# Schematics.net
KiCad netlist of a schematic drawn in Altium Designer
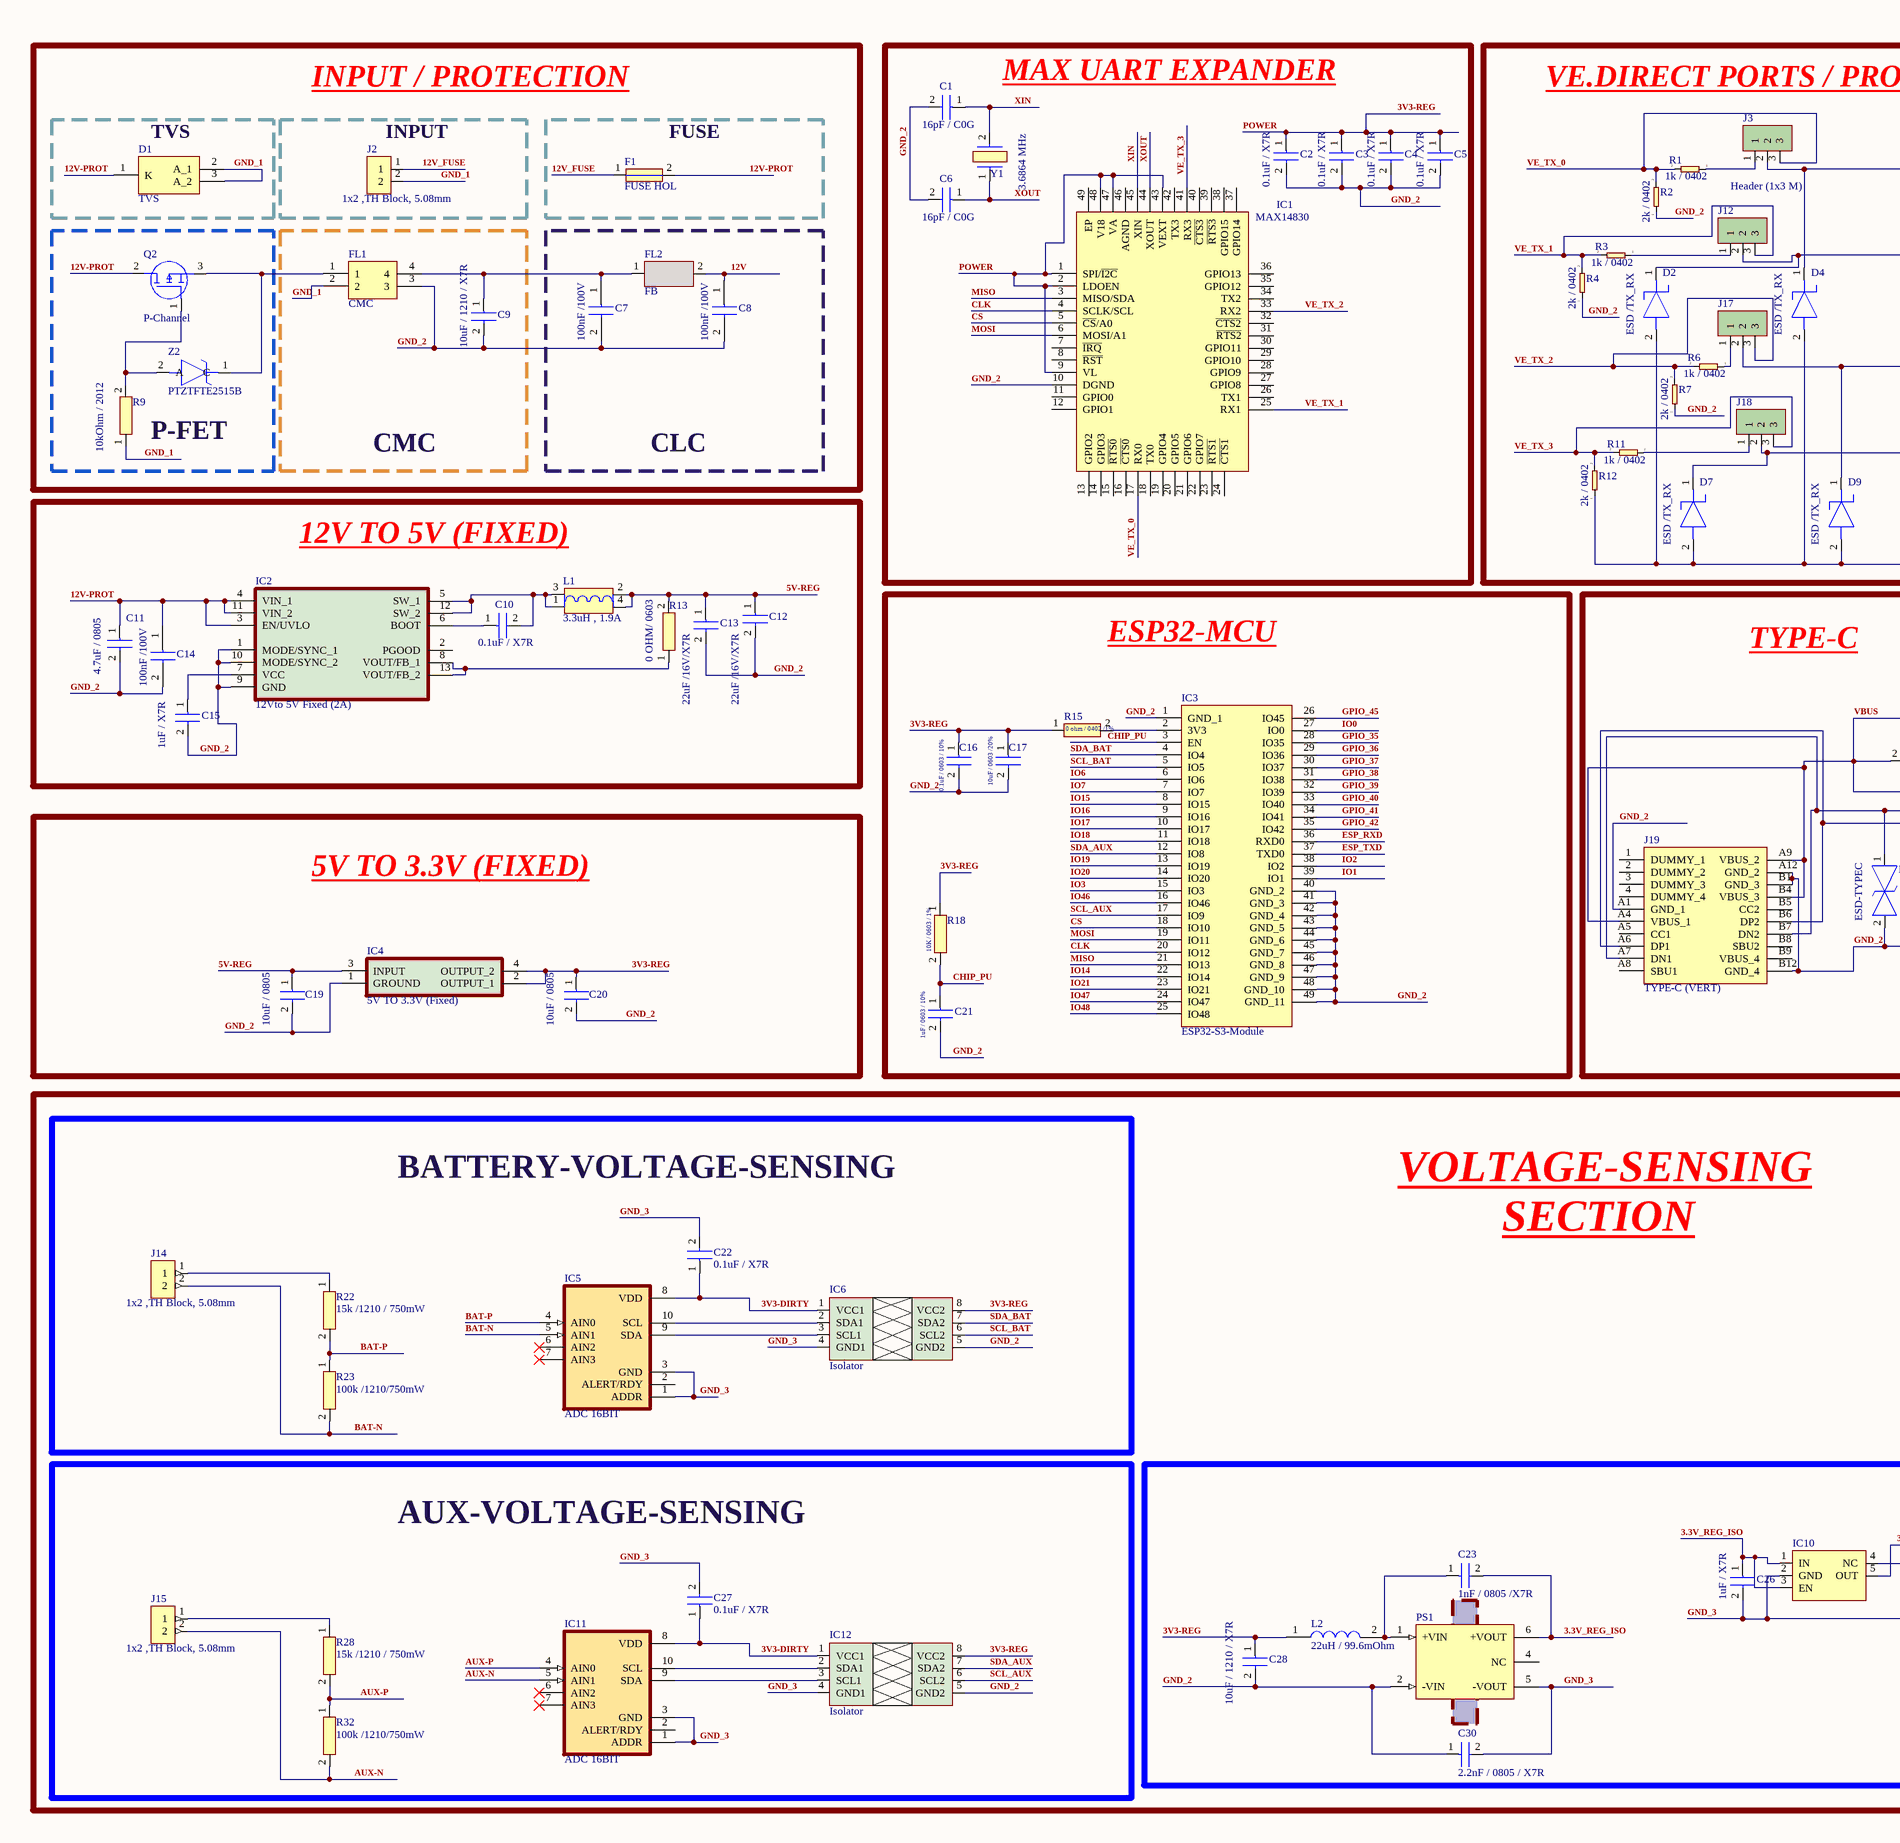
[diagram p0: Schematics.SchDoc, left]
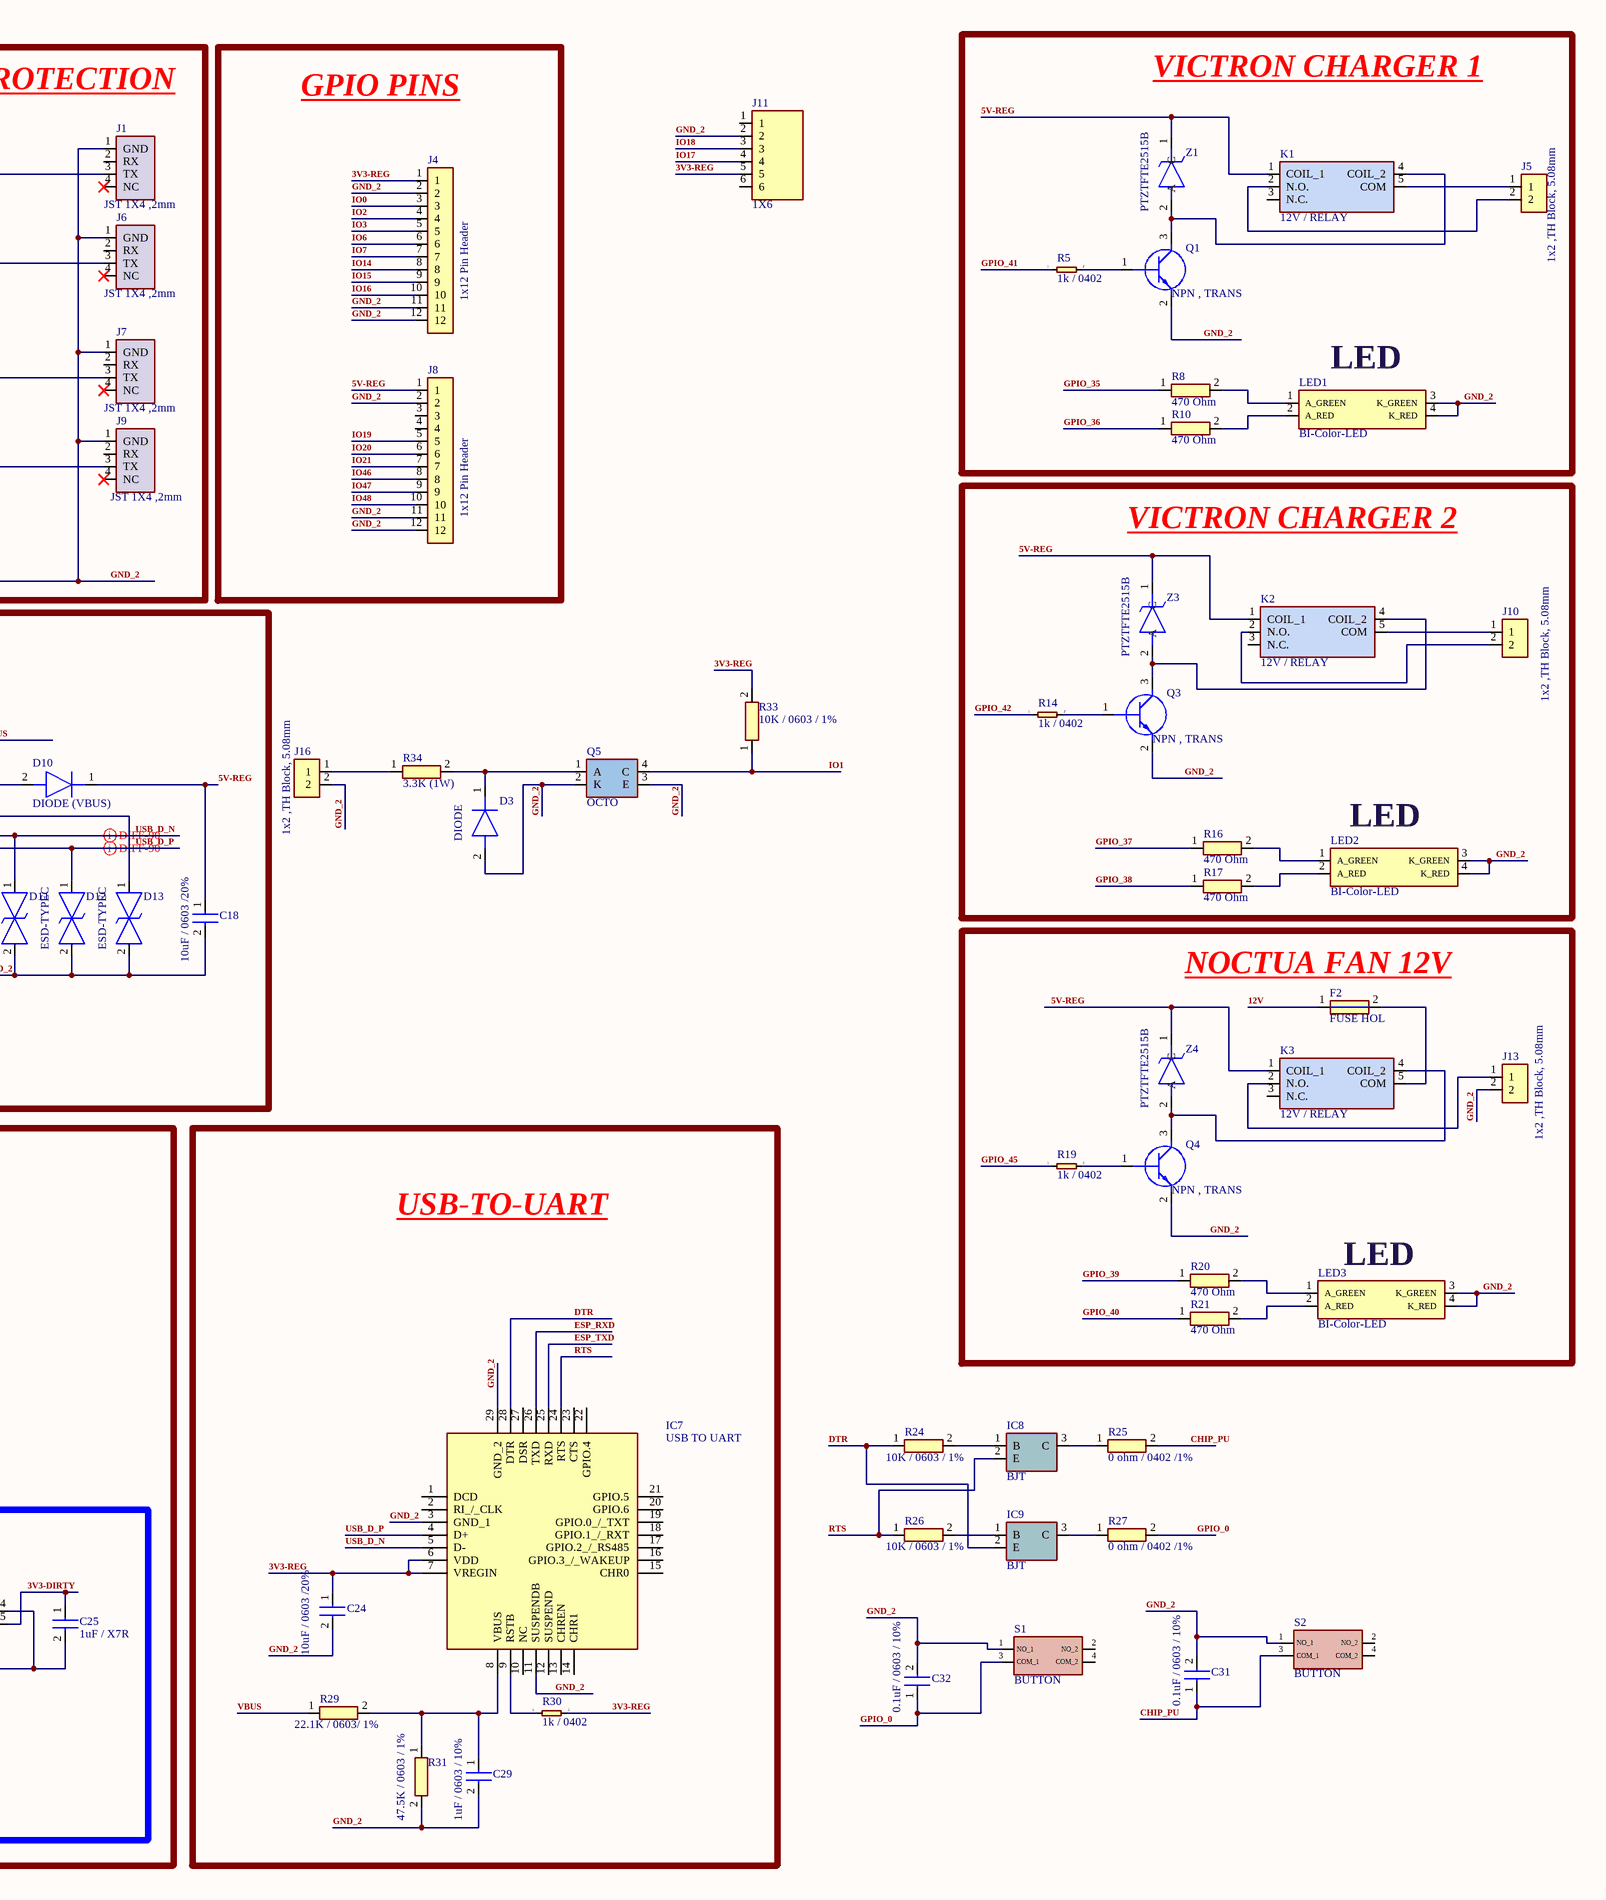
[diagram p1: Schematics.SchDoc, right]

(export (version "E")
  (design (tool "Eeschema 10.0.6"))
  (components
    (comp (ref "C1")
      (value "16pF / C0G")
      (footprint "Project-SCH_Lib:GJM1555C1H170JB01J")
      (description "Capacitor")
      (fields
        (field (name "MANUFACTURER_PART_NUMBER") "GJM1555C1H160FB01J")
        (field (name "MOUSER PART NUMBER") "81-GJM1555C1H160FB1J")
      )
      (libsource (lib "Project-SCH_Lib") (part "GJM1555C1H160FB01J"))
    )
    (comp (ref "C2")
      (value "0.1uF / X7R")
      (footprint "MAJx16")
      (description "Capacitor")
      (fields (field (name "MANUFACTURER_PART_NUMBER") "MAJCU168BB7104KTEA01"))
      (libsource (lib "Project-SCH_Lib") (part "MAJCU168BB7104KTEA01"))
    )
    (comp (ref "C3")
      (value "0.1uF / X7R")
      (footprint "MAJx16")
      (description "Capacitor")
      (fields (field (name "MANUFACTURER_PART_NUMBER") "MAJCU168BB7104KTEA01"))
      (libsource (lib "Project-SCH_Lib") (part "MAJCU168BB7104KTEA01"))
    )
    (comp (ref "C4")
      (value "0.1uF / X7R")
      (footprint "MAJx16")
      (description "Capacitor")
      (fields (field (name "MANUFACTURER_PART_NUMBER") "MAJCU168BB7104KTEA01"))
      (libsource (lib "Project-SCH_Lib") (part "MAJCU168BB7104KTEA01"))
    )
    (comp (ref "C5")
      (value "0.1uF / X7R")
      (footprint "MAJx16")
      (description "Capacitor")
      (fields (field (name "MANUFACTURER_PART_NUMBER") "MAJCU168BB7104KTEA01"))
      (libsource (lib "Project-SCH_Lib") (part "MAJCU168BB7104KTEA01"))
    )
    (comp (ref "C6")
      (value "16pF / C0G")
      (footprint "Project-SCH_Lib:GJM1555C1H170JB01J")
      (description "Capacitor")
      (fields
        (field (name "MANUFACTURER_PART_NUMBER") "GJM1555C1H160FB01J")
        (field (name "MOUSER PART NUMBER") "81-GJM1555C1H160FB1J")
      )
      (libsource (lib "Project-SCH_Lib") (part "GJM1555C1H160FB01J"))
    )
    (comp (ref "C7")
      (value "100nF /100V")
      (footprint "AVCF-PCB_Lib:CAPC1608X87N")
      (description "Multilayer Ceramic Capacitors MLCC - SMD/SMT 100V 100000pF 5% X7R 1608 AEC-Q200")
      (fields
        (field (name "MANUFACTURER_PART_NUMBER") "C0603C104J1RACAUTO7411")
        (field (name "MOUSER PART NUMBER") "80-C0603C104J1RAUTO7")
      )
      (libsource (lib "Project-SCH_Lib") (part "C0603C104J1RACAUTO7411"))
    )
    (comp (ref "C8")
      (value "100nF /100V")
      (footprint "AVCF-PCB_Lib:CAPC1608X87N")
      (description "Multilayer Ceramic Capacitors MLCC - SMD/SMT 100V 100000pF 5% X7R 1608 AEC-Q200")
      (fields
        (field (name "MANUFACTURER_PART_NUMBER") "C0603C104J1RACAUTO7411")
        (field (name "MOUSER PART NUMBER") "80-C0603C104J1RAUTO7")
      )
      (libsource (lib "Project-SCH_Lib") (part "C0603C104J1RACAUTO7411"))
    )
    (comp (ref "C9")
      (value "10uF / 1210 / X7R")
      (footprint "Project-SCH_Lib:CAPC3225X280N")
      (description "Capacitor")
      (fields (field (name "MANUFACTURER_PART_NUMBER") "CGA6P1X7R2A106K250AC"))
      (libsource (lib "Project-SCH_Lib") (part "CGA6P1X7R2A106K250AC"))
    )
    (comp (ref "C10")
      (value "0.1uF / X7R")
      (footprint "MAJx16")
      (description "Capacitor")
      (fields (field (name "MANUFACTURER_PART_NUMBER") "MAJCU168BB7104KTEA01"))
      (libsource (lib "Project-SCH_Lib") (part "MAJCU168BB7104KTEA01"))
    )
    (comp (ref "C11")
      (value "4.7uF / 0805")
      (footprint "AVCF-PCB_Lib:CGA4J2NP01H223J125AA")
      (description "Capacitor")
      (fields
        (field (name "MANUFACTURER_PART_NUMBER") "CGA4J3X7R1C475K125AE")
        (field (name "MOUSER PART NUMBER") "810-CGA4J3X7R1C475KS")
      )
      (libsource (lib "Project-SCH_Lib") (part "CGA4J3X7R1C475K125AE"))
    )
    (comp (ref "C12")
      (value "22uF /16V/X7R")
      (footprint "AVCF-PCB_Lib:CAPC3225X280N")
      (description "Capacitor")
      (fields
        (field (name "MANUFACTURER_PART_NUMBER") "CGA6P1X7R1C226M250AC")
        (field (name "MOUSER PART NUMBER") "810-CGA6P1X7R1C226M")
      )
      (libsource (lib "Project-SCH_Lib") (part "CGA6P1X7R1C226M250AC"))
    )
    (comp (ref "C13")
      (value "22uF /16V/X7R")
      (footprint "AVCF-PCB_Lib:CAPC3225X280N")
      (description "Capacitor")
      (fields
        (field (name "MANUFACTURER_PART_NUMBER") "CGA6P1X7R1C226M250AC")
        (field (name "MOUSER PART NUMBER") "810-CGA6P1X7R1C226M")
      )
      (libsource (lib "Project-SCH_Lib") (part "CGA6P1X7R1C226M250AC"))
    )
    (comp (ref "C14")
      (value "100nF /100V")
      (footprint "AVCF-PCB_Lib:CAPC1608X87N")
      (description "Multilayer Ceramic Capacitors MLCC - SMD/SMT 100V 100000pF 5% X7R 1608 AEC-Q200")
      (fields
        (field (name "MANUFACTURER_PART_NUMBER") "C0603C104J1RACAUTO7411")
        (field (name "MOUSER PART NUMBER") "80-C0603C104J1RAUTO7")
      )
      (libsource (lib "Project-SCH_Lib") (part "C0603C104J1RACAUTO7411"))
    )
    (comp (ref "C15")
      (value "1uF / X7R")
      (footprint "CAPC1608X100N")
      (description "Capacitor")
      (fields
        (field (name "MANUFACTURER_PART_NUMBER") "CL10B105KB9VPNC")
        (field (name "MOUSER PART NUMBER") "187-CL10B105KB9VPNC")
      )
      (libsource (lib "Project-SCH_Lib") (part "CL10B105KB9VPNC"))
    )
    (comp (ref "C16")
      (value "0.1uF / 0603 / 10%")
      (footprint "Project-SCH_Lib:CAPC1608X90N")
      (description "Multilayer Ceramic Capacitors MLCC - SMD/SMT CGA 0603 25V 0.1uF X7R 10% AEC-Q200")
      (fields
        (field (name "MANUFACTURER_PART_NUMBER") "CGA3E2X7R1E104K080AA")
        (field (name "MOUSER PART NUMBER") "810-CGA3E2X7R1E104K")
      )
      (libsource (lib "Project-SCH_Lib") (part "CGA3E2X7R1E104K080AA"))
    )
    (comp (ref "C17")
      (value "10uF / 0603 /20%")
      (footprint "Project-SCH_Lib:CAPC1608X90N")
      (description "Multilayer Ceramic Capacitors MLCC - SMD/SMT 10 uF 25 VDC 20% 0603 X5R AEC-Q200")
      (fields
        (field (name "MANUFACTURER_PART_NUMBER") "GRT188R61E106ME13D")
        (field (name "MOUSER PART NUMBER") "81-GRT188R61E106ME3D")
      )
      (libsource (lib "Project-SCH_Lib") (part "GRT188R61E106ME13D"))
    )
    (comp (ref "C18")
      (value "10uF / 0603 /20%")
      (footprint "Project-SCH_Lib:CAPC1608X90N")
      (description "Multilayer Ceramic Capacitors MLCC - SMD/SMT 10 uF 25 VDC 20% 0603 X5R AEC-Q200")
      (fields
        (field (name "MANUFACTURER_PART_NUMBER") "GRT188R61E106ME13D")
        (field (name "MOUSER PART NUMBER") "81-GRT188R61E106ME3D")
      )
      (libsource (lib "Project-SCH_Lib") (part "GRT188R61E106ME13D"))
    )
    (comp (ref "C19")
      (value "10uF / 0805")
      (footprint "AVCF-PCB_Lib:CGA4J2NP01H223J125AA")
      (description "Capacitor")
      (fields
        (field (name "MANUFACTURER_PART_NUMBER") "CGA4J1X7S1C106M125AE")
        (field (name "MOUSER PART NUMBER") "810-CGA4J1X7S1C106MA")
      )
      (libsource (lib "Project-SCH_Lib") (part "CGA4J1X7S1C106M125AE"))
    )
    (comp (ref "C20")
      (value "10uF / 0805")
      (footprint "AVCF-PCB_Lib:CGA4J2NP01H223J125AA")
      (description "Capacitor")
      (fields
        (field (name "MANUFACTURER_PART_NUMBER") "CGA4J1X7S1C106M125AE")
        (field (name "MOUSER PART NUMBER") "810-CGA4J1X7S1C106MA")
      )
      (libsource (lib "Project-SCH_Lib") (part "CGA4J1X7S1C106M125AE"))
    )
    (comp (ref "C21")
      (value "1uF / 0603 / 10%")
      (footprint "Project-SCH_Lib:CAPC1608X90N")
      (description "Multilayer Ceramic Capacitors MLCC - SMD/SMT SOFT 0603 25V 1uF X7R 10% AEC-Q200")
      (fields
        (field (name "MANUFACTURER_PART_NUMBER") "CGA3E1X7R1E105K080AE")
        (field (name "MOUSER PART NUMBER") "810-CGA3E1X7R1E105KA")
      )
      (libsource (lib "Project-SCH_Lib") (part "CGA3E1X7R1E105K080AE"))
    )
    (comp (ref "C22")
      (value "0.1uF / X7R")
      (footprint "MAJx16")
      (description "Capacitor")
      (fields (field (name "MANUFACTURER_PART_NUMBER") "MAJCU168BB7104KTEA01"))
      (libsource (lib "Project-SCH_Lib") (part "MAJCU168BB7104KTEA01"))
    )
    (comp (ref "C23")
      (value "1nF / 0805 /X7R")
      (footprint "Project-SCH_Lib:C0805")
      (description "Multilayer Ceramic Capacitors MLCC - SMD/SMT 100V 1000pF X7R 0805 20% AEC-Q200")
      (fields
        (field (name "MANUFACTURER_PART_NUMBER") "C0805J222K1RACAUTO")
        (field (name "MOUSER PART NUMBER") "80-C0805J222K1RAUTO")
      )
      (libsource (lib "Project-SCH_Lib") (part "C0805J222K1RACAUTO_1"))
    )
    (comp (ref "C24")
      (value "10uF / 0603 /20%")
      (footprint "Project-SCH_Lib:CAPC1608X90N")
      (description "Multilayer Ceramic Capacitors MLCC - SMD/SMT 10 uF 25 VDC 20% 0603 X5R AEC-Q200")
      (fields
        (field (name "MANUFACTURER_PART_NUMBER") "GRT188R61E106ME13D")
        (field (name "MOUSER PART NUMBER") "81-GRT188R61E106ME3D")
      )
      (libsource (lib "Project-SCH_Lib") (part "GRT188R61E106ME13D"))
    )
    (comp (ref "C25")
      (value "1uF / X7R")
      (footprint "CAPC1608X100N")
      (description "Capacitor")
      (fields
        (field (name "MANUFACTURER_PART_NUMBER") "CL10B105KB9VPNC")
        (field (name "MOUSER PART NUMBER") "187-CL10B105KB9VPNC")
      )
      (libsource (lib "Project-SCH_Lib") (part "CL10B105KB9VPNC"))
    )
    (comp (ref "C26")
      (value "1uF / X7R")
      (footprint "CAPC1608X100N")
      (description "Capacitor")
      (fields
        (field (name "MANUFACTURER_PART_NUMBER") "CL10B105KB9VPNC")
        (field (name "MOUSER PART NUMBER") "187-CL10B105KB9VPNC")
      )
      (libsource (lib "Project-SCH_Lib") (part "CL10B105KB9VPNC"))
    )
    (comp (ref "C27")
      (value "0.1uF / X7R")
      (footprint "MAJx16")
      (description "Capacitor")
      (fields (field (name "MANUFACTURER_PART_NUMBER") "MAJCU168BB7104KTEA01"))
      (libsource (lib "Project-SCH_Lib") (part "MAJCU168BB7104KTEA01"))
    )
    (comp (ref "C28")
      (value "10uF / 1210 / X7R")
      (footprint "Project-SCH_Lib:CAPC3225X280N")
      (description "Capacitor")
      (fields (field (name "MANUFACTURER_PART_NUMBER") "CGA6P1X7R2A106K250AC"))
      (libsource (lib "Project-SCH_Lib") (part "CGA6P1X7R2A106K250AC"))
    )
    (comp (ref "C29")
      (value "1uF / 0603 / 10%")
      (footprint "Project-SCH_Lib:CAPC1608X90N")
      (description "Multilayer Ceramic Capacitors MLCC - SMD/SMT SOFT 0603 25V 1uF X7R 10% AEC-Q200")
      (fields
        (field (name "MANUFACTURER_PART_NUMBER") "CGA3E1X7R1E105K080AE")
        (field (name "MOUSER PART NUMBER") "810-CGA3E1X7R1E105KA")
      )
      (libsource (lib "Project-SCH_Lib") (part "CGA3E1X7R1E105K080AE"))
    )
    (comp (ref "C30")
      (value "2.2nF / 0805 / X7R")
      (footprint "Project-SCH_Lib:C0805")
      (description "Multilayer Ceramic Capacitors MLCC - SMD/SMT 100V 2200pF X7R 0805 10% AEC-Q200")
      (fields
        (field (name "MANUFACTURER_PART_NUMBER") "C0805J222K1RACAUTO")
        (field (name "MOUSER PART NUMBER") "80-C0805J222K1RAUTO")
      )
      (libsource (lib "Project-SCH_Lib") (part "C0805J222K1RACAUTO"))
    )
    (comp (ref "C31")
      (value "0.1uF / 0603 / 10%")
      (footprint "Project-SCH_Lib:CAPC1608X90N")
      (description "Multilayer Ceramic Capacitors MLCC - SMD/SMT CGA 0603 25V 0.1uF X7R 10% AEC-Q200")
      (fields
        (field (name "MANUFACTURER_PART_NUMBER") "CGA3E2X7R1E104K080AA")
        (field (name "MOUSER PART NUMBER") "810-CGA3E2X7R1E104K")
      )
      (libsource (lib "Project-SCH_Lib") (part "CGA3E2X7R1E104K080AA"))
    )
    (comp (ref "C32")
      (value "0.1uF / 0603 / 10%")
      (footprint "Project-SCH_Lib:CAPC1608X90N")
      (description "Multilayer Ceramic Capacitors MLCC - SMD/SMT CGA 0603 25V 0.1uF X7R 10% AEC-Q200")
      (fields
        (field (name "MANUFACTURER_PART_NUMBER") "CGA3E2X7R1E104K080AA")
        (field (name "MOUSER PART NUMBER") "810-CGA3E2X7R1E104K")
      )
      (libsource (lib "Project-SCH_Lib") (part "CGA3E2X7R1E104K080AA"))
    )
    (comp (ref "D1")
      (value "TVS")
      (footprint "AVCF-PCB_Lib:SLD8S36A")
      (description "TVS Diode (Uni-directional)")
      (fields
        (field (name "MANUFACTURER_PART_NUMBER") "SLD8S36A")
        (field (name "MOUSER PART NUMBER") "576-SLD8S36A")
      )
      (libsource (lib "Project-SCH_Lib") (part "SLD8S36A"))
    )
    (comp (ref "D2")
      (value "ESD /TX_RX")
      (footprint "Project-SCH_Lib:PESD5V0S1ULQYL")
      (description "Diode ESD (Uni-directional)")
      (fields
        (field (name "MANUFACTURER_PART_NUMBER") "PESD5V0S1UL-QYL")
        (field (name "MOUSER PART NUMBER") "771-PESD5V0S1UL-QYL")
      )
      (libsource (lib "Project-SCH_Lib") (part "PESD5V0S1UL-QYL"))
    )
    (comp (ref "D3")
      (value "DIODE")
      (footprint "Project-SCH_Lib:SOD3716X125N")
      (description "Diode")
      (fields (field (name "MANUFACTURER_PART_NUMBER") "1N5819HW-7-F"))
      (libsource (lib "Project-SCH_Lib") (part "1N5819HW-7-F"))
    )
    (comp (ref "D4")
      (value "ESD /TX_RX")
      (footprint "Project-SCH_Lib:PESD5V0S1ULQYL")
      (description "Diode ESD (Uni-directional)")
      (fields
        (field (name "MANUFACTURER_PART_NUMBER") "PESD5V0S1UL-QYL")
        (field (name "MOUSER PART NUMBER") "771-PESD5V0S1UL-QYL")
      )
      (libsource (lib "Project-SCH_Lib") (part "PESD5V0S1UL-QYL"))
    )
    (comp (ref "D7")
      (value "ESD /TX_RX")
      (footprint "Project-SCH_Lib:PESD5V0S1ULQYL")
      (description "Diode ESD (Uni-directional)")
      (fields
        (field (name "MANUFACTURER_PART_NUMBER") "PESD5V0S1UL-QYL")
        (field (name "MOUSER PART NUMBER") "771-PESD5V0S1UL-QYL")
      )
      (libsource (lib "Project-SCH_Lib") (part "PESD5V0S1UL-QYL"))
    )
    (comp (ref "D9")
      (value "ESD /TX_RX")
      (footprint "Project-SCH_Lib:PESD5V0S1ULQYL")
      (description "Diode ESD (Uni-directional)")
      (fields
        (field (name "MANUFACTURER_PART_NUMBER") "PESD5V0S1UL-QYL")
        (field (name "MOUSER PART NUMBER") "771-PESD5V0S1UL-QYL")
      )
      (libsource (lib "Project-SCH_Lib") (part "PESD5V0S1UL-QYL"))
    )
    (comp (ref "D10")
      (value "DIODE (VBUS)")
      (footprint "Project-SCH_Lib:SOD3716X125N")
      (description "Diode")
      (fields (field (name "MANUFACTURER_PART_NUMBER") "1N5819HW-7-F"))
      (libsource (lib "Project-SCH_Lib") (part "1N5819HW-7-F"))
    )
    (comp (ref "D11")
      (value "ESD-TYPEC")
      (footprint "Project-SCH_Lib:LESD5D50CT1G")
      (description "TVS Diode (Bi-directional)")
      (fields (field (name "MANUFACTURER_PART_NUMBER") "LESD5D5.0CT1G"))
      (libsource (lib "Project-SCH_Lib") (part "LESD5D5.0CT1G"))
    )
    (comp (ref "D12")
      (value "ESD-TYPEC")
      (footprint "Project-SCH_Lib:LESD5D50CT1G")
      (description "TVS Diode (Bi-directional)")
      (fields (field (name "MANUFACTURER_PART_NUMBER") "LESD5D5.0CT1G"))
      (libsource (lib "Project-SCH_Lib") (part "LESD5D5.0CT1G"))
    )
    (comp (ref "D13")
      (value "ESD-TYPEC")
      (footprint "Project-SCH_Lib:LESD5D50CT1G")
      (description "TVS Diode (Bi-directional)")
      (fields (field (name "MANUFACTURER_PART_NUMBER") "LESD5D5.0CT1G"))
      (libsource (lib "Project-SCH_Lib") (part "LESD5D5.0CT1G"))
    )
    (comp (ref "F1")
      (value "FUSE HOL")
      (footprint "ESP-P4-PCB_LIB:01530008")
      (description "Fuse Holder 15 A 32V 1 Circuit Blade Through Hole")
      (fields
        (field (name "MANUFACTURER_PART_NUMBER") "01530008Z")
        (field (name "MOUSER PART NUMBER") "576-01530008Z")
      )
      (libsource (lib "Project-SCH_Lib") (part "01530008Z"))
    )
    (comp (ref "F2")
      (value "FUSE HOL")
      (footprint "ESP-P4-PCB_LIB:01530008")
      (description "Fuse Holder 15 A 32V 1 Circuit Blade Through Hole")
      (fields
        (field (name "MANUFACTURER_PART_NUMBER") "01530008Z")
        (field (name "MOUSER PART NUMBER") "576-01530008Z")
      )
      (libsource (lib "Project-SCH_Lib") (part "01530008Z"))
    )
    (comp (ref "FL1")
      (value "CMC")
      (footprint "ACT45B1012PTL003")
      (description "Filter")
      (fields
        (field (name "MANUFACTURER_PART_NUMBER") "ACT45B-510-2P-TL003")
        (field (name "MOUSER PART NUMBER") "810-ACT45B5102PTL003")
      )
      (libsource (lib "Project-SCH_Lib") (part "ACT45B-510-2P-TL003"))
    )
    (comp (ref "FL2")
      (value "FB")
      (footprint "BLM31KN102BH1L")
      (description "Filter")
      (fields
        (field (name "MANUFACTURER_PART_NUMBER") "BLM31KN601SZ1L")
        (field (name "MOUSER PART NUMBER") "81-BLM31KN601SZ1L")
      )
      (libsource (lib "Project-SCH_Lib") (part "BLM31KN601SZ1L"))
    )
    (comp (ref "IC1")
      (value "MAX14830")
      (footprint "Project-SCH_Lib:QFN50P700X700X80-49N")
      (description "UART Interface IC Quad Serial UART")
      (fields
        (field (name "MANUFACTURER_PART_NUMBER") "MAX14830ETM+")
        (field (name "MOUSER PART NUMBER") "700-MAX14830ETM+")
      )
      (libsource (lib "Project-SCH_Lib") (part "MAX14830ETM+"))
    )
    (comp (ref "IC2")
      (value "12Vto 5V Fixed (2A)")
      (footprint "Project-SCH_Lib:LMR43620MC5RPERQ1")
      (description "Integrated Circuit")
      (fields (field (name "MANUFACTURER_PART_NUMBER") "LMR43620MSC5RPERQ1"))
      (libsource (lib "Project-SCH_Lib") (part "LMR43620MSC5RPERQ1"))
    )
    (comp (ref "IC3")
      (value "ESP32-S3-Module")
      (footprint "Project-SCH_Lib:ESP32S3WROOM1N8R2")
      (description "WiFi 802.11a/b/g/n, Bluetooth v5.0 Transceiver Module 2.4GHz PCB Trace")
      (fields
        (field (name "MANUFACTURER_PART_NUMBER") "ESP32-S3-WROOM-1-N8")
        (field (name "MOUSER PART NUMBER") "356-ESP32-S3WROOM1N8")
      )
      (libsource (lib "Project-SCH_Lib") (part "ESP32-S3-WROOM-1-N8"))
    )
    (comp (ref "IC4")
      (value "5V TO 3.3V (Fixed)")
      (footprint "Project-SCH_Lib:SOT230P700X180-4N")
      (description "Integrated Circuit")
      (fields
        (field (name "MANUFACTURER_PART_NUMBER") "NCV1117ST33T3G")
        (field (name "MOUSER PART NUMBER") "863-NCV1117ST33T3G")
      )
      (libsource (lib "Project-SCH_Lib") (part "NCV1117ST33T3G"))
    )
    (comp (ref "IC5")
      (value "ADC 16BIT")
      (footprint "Project-SCH_Lib:RUG-(R-PQFP-N10)")
      (description "16 Bit Analog to Digital Converter 2, 4 Input 1 Sigma-Delta 10-X2QFN (2x1.5)")
      (fields
        (field (name "MANUFACTURER_PART_NUMBER") "ADS1115IRUGT")
        (field (name "MOUSER PART NUMBER") "595-ADS1115IRUGT")
      )
      (libsource (lib "Project-SCH_Lib") (part "ADS1115IRUGT"))
    )
    (comp (ref "IC6")
      (value "Isolator")
      (footprint "Project-SCH_Lib:SOIC127P600X175-8N")
      (description "Integrated Circuit")
      (fields
        (field (name "MANUFACTURER_PART_NUMBER") "ISO1540DR")
        (field (name "MOUSER PART NUMBER") "595-ISO1540DR")
      )
      (libsource (lib "Project-SCH_Lib") (part "ISO1540DR"))
    )
    (comp (ref "IC7")
      (value "USB TO UART")
      (footprint "Project-SCH_Lib:QFN50P500X500X80-29N-D")
      (description "USB Bridge, USB to UART USB 2.0 UART Interface 28-QFN (5x5)")
      (fields
        (field (name "MANUFACTURER_PART_NUMBER") "CP2102N-A02-GQFN28R")
        (field (name "MOUSER PART NUMBER") "634-CP2102NA02QFN28R")
      )
      (libsource (lib "Project-SCH_Lib") (part "CP2102N-A02-GQFN28R"))
    )
    (comp (ref "IC8")
      (value "BJT")
      (footprint "SamacSys:L8050QLT1G")
      (description "Integrated Circuit")
      (fields (field (name "MANUFACTURER_PART_NUMBER") "L8050QLT1G"))
      (libsource (lib "Project-SCH_Lib") (part "L8050QLT1G"))
    )
    (comp (ref "IC9")
      (value "BJT")
      (footprint "SamacSys:L8050QLT1G")
      (description "Integrated Circuit")
      (fields (field (name "MANUFACTURER_PART_NUMBER") "L8050QLT1G"))
      (libsource (lib "Project-SCH_Lib") (part "L8050QLT1G"))
    )
    (comp (ref "IC10")
      (value "~")
      (footprint "SOT95P280X145-5N")
      (description "Linear Voltage Regulator IC Positive Fixed 1 Output 300mA SOT-23-5")
      (fields
        (field (name "MANUFACTURER_PART_NUMBER") "TLV70233PDBVT")
        (field (name "MOUSER PART NUMBER") "595-TLV70233PDBVT")
      )
      (libsource (lib "Project-SCH_Lib") (part "TLV70233PDBVT"))
    )
    (comp (ref "IC11")
      (value "ADC 16BIT")
      (footprint "Project-SCH_Lib:RUG-(R-PQFP-N10)")
      (description "16 Bit Analog to Digital Converter 2, 4 Input 1 Sigma-Delta 10-X2QFN (2x1.5)")
      (fields
        (field (name "MANUFACTURER_PART_NUMBER") "ADS1115IRUGT")
        (field (name "MOUSER PART NUMBER") "595-ADS1115IRUGT")
      )
      (libsource (lib "Project-SCH_Lib") (part "ADS1115IRUGT"))
    )
    (comp (ref "IC12")
      (value "Isolator")
      (footprint "Project-SCH_Lib:SOIC127P600X175-8N")
      (description "Integrated Circuit")
      (fields
        (field (name "MANUFACTURER_PART_NUMBER") "ISO1540DR")
        (field (name "MOUSER PART NUMBER") "595-ISO1540DR")
      )
      (libsource (lib "Project-SCH_Lib") (part "ISO1540DR"))
    )
    (comp (ref "J1")
      (value "JST 1X4 ,2mm")
      (footprint "Project-SCH_Lib:SHDR4W50P0X200_1X4_990X600X450P")
      (description "Connector")
      (fields (field (name "MANUFACTURER_PART_NUMBER") "455-1706-ND"))
      (libsource (lib "Project-SCH_Lib") (part "455-1706-ND"))
    )
    (comp (ref "J2")
      (value "1x2 ,TH Block, 5.08mm")
      (footprint "Project-SCH_Lib:1760510000")
      (description "2 Position Wire to Board Terminal Block Horizontal with Board 0.200\" (5.08mm) Through Hole")
      (fields
        (field (name "MANUFACTURER_PART_NUMBER") "1760510000")
        (field (name "MOUSER PART NUMBER") "470-1760510000")
      )
      (libsource (lib "") (part "1760510000_1"))
    )
    (comp (ref "J3")
      (value "Header (1x3 M)")
      (footprint "Project-SCH_Lib:HDRV3W63P0X254_1X3_762X250X950P")
      (description "Connector")
      (fields
        (field (name "MANUFACTURER_PART_NUMBER") "826926-3")
        (field (name "MOUSER PART NUMBER") "571-826926-3")
      )
      (libsource (lib "Project-SCH_Lib") (part "826926-3"))
    )
    (comp (ref "J4")
      (value "1x12 Pin Header")
      (footprint "Project-SCH_Lib:HDRV12W68P0X254_1X12_3048X250X970P")
      (description "Connector")
      (fields
        (field (name "MANUFACTURER_PART_NUMBER") "1-826629-2")
        (field (name "MOUSER PART NUMBER") "571-1-826629-2")
      )
      (libsource (lib "Project-SCH_Lib") (part "1-826629-2"))
    )
    (comp (ref "J5")
      (value "1x2 ,TH Block, 5.08mm")
      (footprint "Project-SCH_Lib:1760510000")
      (description "2 Position Wire to Board Terminal Block Horizontal with Board 0.200\" (5.08mm) Through Hole")
      (fields
        (field (name "MANUFACTURER_PART_NUMBER") "1760510000")
        (field (name "MOUSER PART NUMBER") "470-1760510000")
      )
      (libsource (lib "Project-SCH_Lib") (part "1760510000"))
    )
    (comp (ref "J6")
      (value "JST 1X4 ,2mm")
      (footprint "Project-SCH_Lib:SHDR4W50P0X200_1X4_990X600X450P")
      (description "Connector")
      (fields (field (name "MANUFACTURER_PART_NUMBER") "455-1706-ND"))
      (libsource (lib "Project-SCH_Lib") (part "455-1706-ND"))
    )
    (comp (ref "J7")
      (value "JST 1X4 ,2mm")
      (footprint "Project-SCH_Lib:SHDR4W50P0X200_1X4_990X600X450P")
      (description "Connector")
      (fields (field (name "MANUFACTURER_PART_NUMBER") "455-1706-ND"))
      (libsource (lib "Project-SCH_Lib") (part "455-1706-ND"))
    )
    (comp (ref "J8")
      (value "1x12 Pin Header")
      (footprint "Project-SCH_Lib:HDRV12W68P0X254_1X12_3048X250X970P")
      (description "Connector")
      (fields
        (field (name "MANUFACTURER_PART_NUMBER") "1-826629-2")
        (field (name "MOUSER PART NUMBER") "571-1-826629-2")
      )
      (libsource (lib "Project-SCH_Lib") (part "1-826629-2"))
    )
    (comp (ref "J9")
      (value "JST 1X4 ,2mm")
      (footprint "Project-SCH_Lib:SHDR4W50P0X200_1X4_990X600X450P")
      (description "Connector")
      (fields (field (name "MANUFACTURER_PART_NUMBER") "455-1706-ND"))
      (libsource (lib "Project-SCH_Lib") (part "455-1706-ND"))
    )
    (comp (ref "J10")
      (value "1x2 ,TH Block, 5.08mm")
      (footprint "Project-SCH_Lib:1760510000")
      (description "2 Position Wire to Board Terminal Block Horizontal with Board 0.200\" (5.08mm) Through Hole")
      (fields
        (field (name "MANUFACTURER_PART_NUMBER") "1760510000")
        (field (name "MOUSER PART NUMBER") "470-1760510000")
      )
      (libsource (lib "Project-SCH_Lib") (part "1760510000"))
    )
    (comp (ref "J11")
      (value "1X6")
      (footprint "Project-SCH_Lib:68001206HLF")
      (description "Connector")
      (fields
        (field (name "MANUFACTURER_PART_NUMBER") "68001-206HLF")
        (field (name "MOUSER PART NUMBER") "649-68001-206HLF")
      )
      (libsource (lib "Project-SCH_Lib") (part "68001-206HLF"))
    )
    (comp (ref "J12")
      (value "Header (1x3 M)")
      (footprint "Project-SCH_Lib:HDRV3W63P0X254_1X3_762X250X950P")
      (description "Connector")
      (fields
        (field (name "MANUFACTURER_PART_NUMBER") "826926-3")
        (field (name "MOUSER PART NUMBER") "571-826926-3")
      )
      (libsource (lib "Project-SCH_Lib") (part "826926-3"))
    )
    (comp (ref "J13")
      (value "1x2 ,TH Block, 5.08mm")
      (footprint "Project-SCH_Lib:1760510000")
      (description "2 Position Wire to Board Terminal Block Horizontal with Board 0.200\" (5.08mm) Through Hole")
      (fields
        (field (name "MANUFACTURER_PART_NUMBER") "1760510000")
        (field (name "MOUSER PART NUMBER") "470-1760510000")
      )
      (libsource (lib "Project-SCH_Lib") (part "1760510000"))
    )
    (comp (ref "J14")
      (value "1x2 ,TH Block, 5.08mm")
      (footprint "Project-SCH_Lib:1760510000")
      (description "2 Position Wire to Board Terminal Block Horizontal with Board 0.200\" (5.08mm) Through Hole")
      (fields
        (field (name "MANUFACTURER_PART_NUMBER") "1760510000")
        (field (name "MOUSER PART NUMBER") "470-1760510000")
      )
      (libsource (lib "") (part "1760510000_1"))
    )
    (comp (ref "J15")
      (value "1x2 ,TH Block, 5.08mm")
      (footprint "Project-SCH_Lib:1760510000")
      (description "2 Position Wire to Board Terminal Block Horizontal with Board 0.200\" (5.08mm) Through Hole")
      (fields
        (field (name "MANUFACTURER_PART_NUMBER") "1760510000")
        (field (name "MOUSER PART NUMBER") "470-1760510000")
      )
      (libsource (lib "") (part "1760510000_1"))
    )
    (comp (ref "J16")
      (value "1x2 ,TH Block, 5.08mm")
      (footprint "Project-SCH_Lib:1760510000")
      (description "2 Position Wire to Board Terminal Block Horizontal with Board 0.200\" (5.08mm) Through Hole")
      (fields
        (field (name "MANUFACTURER_PART_NUMBER") "1760510000")
        (field (name "MOUSER PART NUMBER") "470-1760510000")
      )
      (libsource (lib "") (part "1760510000_1"))
    )
    (comp (ref "J17")
      (value "Header (1x3 M)")
      (footprint "Project-SCH_Lib:HDRV3W63P0X254_1X3_762X250X950P")
      (description "Connector")
      (fields
        (field (name "MANUFACTURER_PART_NUMBER") "826926-3")
        (field (name "MOUSER PART NUMBER") "571-826926-3")
      )
      (libsource (lib "Project-SCH_Lib") (part "826926-3"))
    )
    (comp (ref "J18")
      (value "Header (1x3 M)")
      (footprint "Project-SCH_Lib:HDRV3W63P0X254_1X3_762X250X950P")
      (description "Connector")
      (fields
        (field (name "MANUFACTURER_PART_NUMBER") "826926-3")
        (field (name "MOUSER PART NUMBER") "571-826926-3")
      )
      (libsource (lib "Project-SCH_Lib") (part "826926-3"))
    )
    (comp (ref "J19")
      (value "TYPE-C (VERT)")
      (footprint "Project-SCH_Lib:UJ20CVGSMTP16TR65")
      (description "USB Connectors Type C, 2.0, Vertical, Gold Plated 3u, Surface Mount, 16 pin, IP65")
      (fields
        (field (name "MANUFACTURER_PART_NUMBER") "UJ20-C-V-G-SMT-P16-TR-65")
        (field (name "MOUSER PART NUMBER") "179-UJ20CVGSMTP16TR6")
      )
      (libsource (lib "Project-SCH_Lib") (part "UJ20-C-V-G-SMT-P16-TR-65"))
    )
    (comp (ref "K1")
      (value "12V / RELAY")
      (footprint "Project-SCH_Lib:ACQ131")
      (description "Relay or Contactor")
      (fields
        (field (name "MANUFACTURER_PART_NUMBER") "ACQ131")
        (field (name "MOUSER PART NUMBER") "769-ACQ131")
      )
      (libsource (lib "Project-SCH_Lib") (part "ACQ131"))
    )
    (comp (ref "K2")
      (value "12V / RELAY")
      (footprint "Project-SCH_Lib:ACQ131")
      (description "Relay or Contactor")
      (fields
        (field (name "MANUFACTURER_PART_NUMBER") "ACQ131")
        (field (name "MOUSER PART NUMBER") "769-ACQ131")
      )
      (libsource (lib "Project-SCH_Lib") (part "ACQ131"))
    )
    (comp (ref "K3")
      (value "12V / RELAY")
      (footprint "Project-SCH_Lib:ACQ131")
      (description "Relay or Contactor")
      (fields
        (field (name "MANUFACTURER_PART_NUMBER") "ACQ131")
        (field (name "MOUSER PART NUMBER") "769-ACQ131")
      )
      (libsource (lib "Project-SCH_Lib") (part "ACQ131"))
    )
    (comp (ref "L1")
      (value "3.3uH , 1.9A")
      (footprint "Project-SCH_Lib:LQH43MN470K03L")
      (description "Inductor")
      (fields
        (field (name "MANUFACTURER_PART_NUMBER") "LQH43PH3R3M26L")
        (field (name "MOUSER PART NUMBER") "81-LQH43PH3R3M26L")
      )
      (libsource (lib "Project-SCH_Lib") (part "LQH43PH3R3M26L"))
    )
    (comp (ref "L2")
      (value "22uH / 99.6mOhm")
      (footprint "XAL5030")
      (description "Inductor")
      (fields
        (field (name "MANUFACTURER_PART_NUMBER") "XAL5050-223MEC")
        (field (name "MOUSER PART NUMBER") "994-XAL5050-223MEC")
      )
      (libsource (lib "Project-SCH_Lib") (part "XAL5050-223MEC"))
    )
    (comp (ref "LED1")
      (value "BI-Color-LED")
      (footprint "Project-SCH_Lib:HSMFC163")
      (description "LED")
      (fields
        (field (name "MANUFACTURER_PART_NUMBER") "HSMF-C163")
        (field (name "MOUSER PART NUMBER") "630-HSMF-C163")
      )
      (libsource (lib "Project-SCH_Lib") (part "HSMF-C163"))
    )
    (comp (ref "LED2")
      (value "BI-Color-LED")
      (footprint "Project-SCH_Lib:HSMFC163")
      (description "LED")
      (fields
        (field (name "MANUFACTURER_PART_NUMBER") "HSMF-C163")
        (field (name "MOUSER PART NUMBER") "630-HSMF-C163")
      )
      (libsource (lib "Project-SCH_Lib") (part "HSMF-C163"))
    )
    (comp (ref "LED3")
      (value "BI-Color-LED")
      (footprint "Project-SCH_Lib:HSMFC163")
      (description "LED")
      (fields
        (field (name "MANUFACTURER_PART_NUMBER") "HSMF-C163")
        (field (name "MOUSER PART NUMBER") "630-HSMF-C163")
      )
      (libsource (lib "Project-SCH_Lib") (part "HSMF-C163"))
    )
    (comp (ref "PS1")
      (value "~")
      (footprint "CONV_RB-3.33.3S")
      (description "1W DC/DC-Converter 'ECONOLINE' SIP7 1kV unreg")
      (fields (field (name "MF") "Recom Power") (field (name "MP") "RB-3.33.3S"))
      (libsource (lib "Project-SCH_Lib") (part "RB-3.33.3S"))
    )
    (comp (ref "Q1")
      (value "NPN , TRANS")
      (footprint "Project-SCH_Lib:SOT95P230X110-3N")
      (description "Transistor BJT NPN")
      (fields
        (field (name "MANUFACTURER_PART_NUMBER") "DI13001")
        (field (name "MOUSER PART NUMBER") "637-DI13001")
      )
      (libsource (lib "Project-SCH_Lib") (part "DI13001"))
    )
    (comp (ref "Q2")
      (value "P-Channel")
      (footprint "FQD20N06TM")
      (description "MOSFET (P-Channel)")
      (fields
        (field (name "MANUFACTURER_PART_NUMBER") "FQD8P10TM-F085")
        (field (name "MOUSER PART NUMBER") "512-FQD8P10TM_F085")
      )
      (libsource (lib "Project-SCH_Lib") (part "FQD8P10TM-F085"))
    )
    (comp (ref "Q3")
      (value "NPN , TRANS")
      (footprint "Project-SCH_Lib:SOT95P230X110-3N")
      (description "Transistor BJT NPN")
      (fields
        (field (name "MANUFACTURER_PART_NUMBER") "DI13001")
        (field (name "MOUSER PART NUMBER") "637-DI13001")
      )
      (libsource (lib "Project-SCH_Lib") (part "DI13001"))
    )
    (comp (ref "Q4")
      (value "NPN , TRANS")
      (footprint "Project-SCH_Lib:SOT95P230X110-3N")
      (description "Transistor BJT NPN")
      (fields
        (field (name "MANUFACTURER_PART_NUMBER") "DI13001")
        (field (name "MOUSER PART NUMBER") "637-DI13001")
      )
      (libsource (lib "Project-SCH_Lib") (part "DI13001"))
    )
    (comp (ref "Q5")
      (value "OCTO")
      (footprint "Project-SCH_Lib:SOP254P1016X436-4N")
      (description "Phototransistor")
      (fields
        (field (name "MANUFACTURER_PART_NUMBER") "PC817X1CSP9F")
        (field (name "MOUSER PART NUMBER") "852-PC817X1CSP9F")
      )
      (libsource (lib "Project-SCH_Lib") (part "PC817X1CSP9F"))
    )
    (comp (ref "R1")
      (value "1k / 0402")
      (footprint "Project-SCH_Lib:ERJ2RKD1004X")
      (description "Thick Film Resistors - SMD 0402 1Kohms 1% AEC-Q200")
      (fields
        (field (name "MANUFACTURER_PART_NUMBER") "ERJ-2RKF1001X")
        (field (name "MOUSER PART NUMBER") "667-ERJ-2RKF1001X")
      )
      (libsource (lib "") (part "ERJ-2RKF1001X_1"))
    )
    (comp (ref "R2")
      (value "2k / 0402")
      (footprint "Project-SCH_Lib:ERJPA2_(0402)")
      (description "Thick Film Resistors - SMD 0402 1%2Kohm")
      (fields
        (field (name "MANUFACTURER_PART_NUMBER") "ERJ-PA2F2001X")
        (field (name "MOUSER PART NUMBER") "667-ERJ-PA2F2001X")
      )
      (libsource (lib "Project-SCH_Lib") (part "ERJ-PA2F2001X"))
    )
    (comp (ref "R3")
      (value "1k / 0402")
      (footprint "Project-SCH_Lib:ERJ2RKD1004X")
      (description "Thick Film Resistors - SMD 0402 1Kohms 1% AEC-Q200")
      (fields
        (field (name "MANUFACTURER_PART_NUMBER") "ERJ-2RKF1001X")
        (field (name "MOUSER PART NUMBER") "667-ERJ-2RKF1001X")
      )
      (libsource (lib "") (part "ERJ-2RKF1001X_1"))
    )
    (comp (ref "R4")
      (value "2k / 0402")
      (footprint "Project-SCH_Lib:ERJPA2_(0402)")
      (description "Thick Film Resistors - SMD 0402 1%2Kohm")
      (fields
        (field (name "MANUFACTURER_PART_NUMBER") "ERJ-PA2F2001X")
        (field (name "MOUSER PART NUMBER") "667-ERJ-PA2F2001X")
      )
      (libsource (lib "Project-SCH_Lib") (part "ERJ-PA2F2001X"))
    )
    (comp (ref "R5")
      (value "1k / 0402")
      (footprint "Project-SCH_Lib:ERJ2RKD1004X")
      (description "Thick Film Resistors - SMD 0402 1Kohms 1% AEC-Q200")
      (fields
        (field (name "MANUFACTURER_PART_NUMBER") "ERJ-2RKF1001X")
        (field (name "MOUSER PART NUMBER") "667-ERJ-2RKF1001X")
      )
      (libsource (lib "Project-SCH_Lib") (part "ERJ-2RKF1001X"))
    )
    (comp (ref "R6")
      (value "1k / 0402")
      (footprint "Project-SCH_Lib:ERJ2RKD1004X")
      (description "Thick Film Resistors - SMD 0402 1Kohms 1% AEC-Q200")
      (fields
        (field (name "MANUFACTURER_PART_NUMBER") "ERJ-2RKF1001X")
        (field (name "MOUSER PART NUMBER") "667-ERJ-2RKF1001X")
      )
      (libsource (lib "") (part "ERJ-2RKF1001X_1"))
    )
    (comp (ref "R7")
      (value "2k / 0402")
      (footprint "Project-SCH_Lib:ERJPA2_(0402)")
      (description "Thick Film Resistors - SMD 0402 1%2Kohm")
      (fields
        (field (name "MANUFACTURER_PART_NUMBER") "ERJ-PA2F2001X")
        (field (name "MOUSER PART NUMBER") "667-ERJ-PA2F2001X")
      )
      (libsource (lib "Project-SCH_Lib") (part "ERJ-PA2F2001X"))
    )
    (comp (ref "R8")
      (value "470 Ohm")
      (footprint "AVCF-PCB_Lib:RESC2012X50N")
      (description "Resistor")
      (fields
        (field (name "MANUFACTURER_PART_NUMBER") "RCS0805470RJNEA")
        (field (name "MOUSER PART NUMBER") "71-RCS0805470RJNEA")
      )
      (libsource (lib "Project-SCH_Lib") (part "RCS0805470RJNEA"))
    )
    (comp (ref "R9")
      (value "10kOhm / 2012")
      (footprint "RESC2012X60N")
      (description "Resistor")
      (fields
        (field (name "MANUFACTURER_PART_NUMBER") "RT0805FRE1010KL")
        (field (name "MOUSER PART NUMBER") "603-RT0805FRE1010KL")
      )
      (libsource (lib "Project-SCH_Lib") (part "RT0805FRE1010KL"))
    )
    (comp (ref "R10")
      (value "470 Ohm")
      (footprint "AVCF-PCB_Lib:RESC2012X50N")
      (description "Resistor")
      (fields
        (field (name "MANUFACTURER_PART_NUMBER") "RCS0805470RJNEA")
        (field (name "MOUSER PART NUMBER") "71-RCS0805470RJNEA")
      )
      (libsource (lib "Project-SCH_Lib") (part "RCS0805470RJNEA"))
    )
    (comp (ref "R11")
      (value "1k / 0402")
      (footprint "Project-SCH_Lib:ERJ2RKD1004X")
      (description "Thick Film Resistors - SMD 0402 1Kohms 1% AEC-Q200")
      (fields
        (field (name "MANUFACTURER_PART_NUMBER") "ERJ-2RKF1001X")
        (field (name "MOUSER PART NUMBER") "667-ERJ-2RKF1001X")
      )
      (libsource (lib "") (part "ERJ-2RKF1001X_1"))
    )
    (comp (ref "R12")
      (value "2k / 0402")
      (footprint "Project-SCH_Lib:ERJPA2_(0402)")
      (description "Thick Film Resistors - SMD 0402 1%2Kohm")
      (fields
        (field (name "MANUFACTURER_PART_NUMBER") "ERJ-PA2F2001X")
        (field (name "MOUSER PART NUMBER") "667-ERJ-PA2F2001X")
      )
      (libsource (lib "Project-SCH_Lib") (part "ERJ-PA2F2001X"))
    )
    (comp (ref "R13")
      (value "0 OHM/ 0603")
      (footprint "Project-SCH_Lib:RESC1608X55N")
      (description "Thick Film Resistors 0603 Zero ohm Jumper 0.05ohm AEC-Q200")
      (fields
        (field (name "MANUFACTURER_PART_NUMBER") "ERJ-S030R00V")
        (field (name "MOUSER PART NUMBER") "667-ERJ-S030R00V")
      )
      (libsource (lib "Project-SCH_Lib") (part "ERJ-S030R00V"))
    )
    (comp (ref "R14")
      (value "1k / 0402")
      (footprint "Project-SCH_Lib:ERJ2RKD1004X")
      (description "Thick Film Resistors - SMD 0402 1Kohms 1% AEC-Q200")
      (fields
        (field (name "MANUFACTURER_PART_NUMBER") "ERJ-2RKF1001X")
        (field (name "MOUSER PART NUMBER") "667-ERJ-2RKF1001X")
      )
      (libsource (lib "Project-SCH_Lib") (part "ERJ-2RKF1001X"))
    )
    (comp (ref "R15")
      (value "0 ohm / 0402 /1%")
      (footprint "Project-SCH_Lib:RESC1005X37N")
      (description "Thick Film Resistors - SMD 0 Ohms 1/16 W 50 V 1% 0402 - 55 C + 155 C AEC-Q200")
      (fields
        (field (name "MANUFACTURER_PART_NUMBER") "AC0402FR-070RL")
        (field (name "MOUSER PART NUMBER") "603-AC0402FR-070RL")
      )
      (libsource (lib "Project-SCH_Lib") (part "AC0402FR-070RL"))
    )
    (comp (ref "R16")
      (value "470 Ohm")
      (footprint "AVCF-PCB_Lib:RESC2012X50N")
      (description "Resistor")
      (fields
        (field (name "MANUFACTURER_PART_NUMBER") "RCS0805470RJNEA")
        (field (name "MOUSER PART NUMBER") "71-RCS0805470RJNEA")
      )
      (libsource (lib "Project-SCH_Lib") (part "RCS0805470RJNEA"))
    )
    (comp (ref "R17")
      (value "470 Ohm")
      (footprint "AVCF-PCB_Lib:RESC2012X50N")
      (description "Resistor")
      (fields
        (field (name "MANUFACTURER_PART_NUMBER") "RCS0805470RJNEA")
        (field (name "MOUSER PART NUMBER") "71-RCS0805470RJNEA")
      )
      (libsource (lib "Project-SCH_Lib") (part "RCS0805470RJNEA"))
    )
    (comp (ref "R18")
      (value "10K / 0603 / 1%")
      (footprint "Project-SCH_Lib:ERJP03_PA3_(0603)")
      (description "Thick Film Resistors - SMD 0603 10Kohms 1% AEC-Q200")
      (fields
        (field (name "MANUFACTURER_PART_NUMBER") "ERJ-3EKF1002V")
        (field (name "MOUSER PART NUMBER") "667-ERJ-3EKF1002V")
      )
      (libsource (lib "") (part "ERJ-3EKF1002V_2"))
    )
    (comp (ref "R19")
      (value "1k / 0402")
      (footprint "Project-SCH_Lib:ERJ2RKD1004X")
      (description "Thick Film Resistors - SMD 0402 1Kohms 1% AEC-Q200")
      (fields
        (field (name "MANUFACTURER_PART_NUMBER") "ERJ-2RKF1001X")
        (field (name "MOUSER PART NUMBER") "667-ERJ-2RKF1001X")
      )
      (libsource (lib "Project-SCH_Lib") (part "ERJ-2RKF1001X"))
    )
    (comp (ref "R20")
      (value "470 Ohm")
      (footprint "AVCF-PCB_Lib:RESC2012X50N")
      (description "Resistor")
      (fields
        (field (name "MANUFACTURER_PART_NUMBER") "RCS0805470RJNEA")
        (field (name "MOUSER PART NUMBER") "71-RCS0805470RJNEA")
      )
      (libsource (lib "Project-SCH_Lib") (part "RCS0805470RJNEA"))
    )
    (comp (ref "R21")
      (value "470 Ohm")
      (footprint "AVCF-PCB_Lib:RESC2012X50N")
      (description "Resistor")
      (fields
        (field (name "MANUFACTURER_PART_NUMBER") "RCS0805470RJNEA")
        (field (name "MOUSER PART NUMBER") "71-RCS0805470RJNEA")
      )
      (libsource (lib "Project-SCH_Lib") (part "RCS0805470RJNEA"))
    )
    (comp (ref "R22")
      (value "15k /1210 / 750mW")
      (footprint "Project-SCH_Lib:RESC3225X70N")
      (description "Resistor")
      (fields
        (field (name "MANUFACTURER_PART_NUMBER") "CRCW121015K0FKEAHP")
        (field (name "MOUSER PART NUMBER") "71-CRCW121015K0FKEAH")
      )
      (libsource (lib "Project-SCH_Lib") (part "CRCW121015K0FKEAHP"))
    )
    (comp (ref "R23")
      (value "100k /1210/750mW")
      (footprint "Project-SCH_Lib:RESC3225X70N")
      (description "Resistor")
      (fields
        (field (name "MANUFACTURER_PART_NUMBER") "CRCW1210100KFKEAHP")
        (field (name "MOUSER PART NUMBER") "71-CRCW1210100KFKEAH")
      )
      (libsource (lib "Project-SCH_Lib") (part "CRCW1210100KFKEAHP"))
    )
    (comp (ref "R24")
      (value "10K / 0603 / 1%")
      (footprint "Project-SCH_Lib:ERJP03_PA3_(0603)")
      (description "Thick Film Resistors - SMD 0603 10Kohms 1% AEC-Q200")
      (fields
        (field (name "MANUFACTURER_PART_NUMBER") "ERJ-3EKF1002V")
        (field (name "MOUSER PART NUMBER") "667-ERJ-3EKF1002V")
      )
      (libsource (lib "") (part "ERJ-3EKF1002V_1"))
    )
    (comp (ref "R25")
      (value "0 ohm / 0402 /1%")
      (footprint "Project-SCH_Lib:RESC1005X37N")
      (description "Thick Film Resistors - SMD 0 Ohms 1/16 W 50 V 1% 0402 - 55 C + 155 C AEC-Q200")
      (fields
        (field (name "MANUFACTURER_PART_NUMBER") "AC0402FR-070RL")
        (field (name "MOUSER PART NUMBER") "603-AC0402FR-070RL")
      )
      (libsource (lib "Project-SCH_Lib") (part "AC0402FR-070RL"))
    )
    (comp (ref "R26")
      (value "10K / 0603 / 1%")
      (footprint "Project-SCH_Lib:ERJP03_PA3_(0603)")
      (description "Thick Film Resistors - SMD 0603 10Kohms 1% AEC-Q200")
      (fields
        (field (name "MANUFACTURER_PART_NUMBER") "ERJ-3EKF1002V")
        (field (name "MOUSER PART NUMBER") "667-ERJ-3EKF1002V")
      )
      (libsource (lib "") (part "ERJ-3EKF1002V_1"))
    )
    (comp (ref "R27")
      (value "0 ohm / 0402 /1%")
      (footprint "Project-SCH_Lib:RESC1005X37N")
      (description "Thick Film Resistors - SMD 0 Ohms 1/16 W 50 V 1% 0402 - 55 C + 155 C AEC-Q200")
      (fields
        (field (name "MANUFACTURER_PART_NUMBER") "AC0402FR-070RL")
        (field (name "MOUSER PART NUMBER") "603-AC0402FR-070RL")
      )
      (libsource (lib "Project-SCH_Lib") (part "AC0402FR-070RL"))
    )
    (comp (ref "R28")
      (value "15k /1210 / 750mW")
      (footprint "Project-SCH_Lib:RESC3225X70N")
      (description "Resistor")
      (fields
        (field (name "MANUFACTURER_PART_NUMBER") "CRCW121015K0FKEAHP")
        (field (name "MOUSER PART NUMBER") "71-CRCW121015K0FKEAH")
      )
      (libsource (lib "Project-SCH_Lib") (part "CRCW121015K0FKEAHP"))
    )
    (comp (ref "R29")
      (value "22.1K / 0603/ 1%")
      (footprint "Project-SCH_Lib:ERJP03_PA3_(0603)")
      (description "Thick Film Resistors - SMD 0603 22.1Kohm 1% Anti-Surge AEC-Q200")
      (fields
        (field (name "MANUFACTURER_PART_NUMBER") "ERJ-PA3F2212V")
        (field (name "MOUSER PART NUMBER") "667-ERJ-PA3F2212V")
      )
      (libsource (lib "Project-SCH_Lib") (part "ERJ-PA3F2212V"))
    )
    (comp (ref "R30")
      (value "1k / 0402")
      (footprint "Project-SCH_Lib:ERJ2RKD1004X")
      (description "Thick Film Resistors - SMD 0402 1Kohms 1% AEC-Q200")
      (fields
        (field (name "MANUFACTURER_PART_NUMBER") "ERJ-2RKF1001X")
        (field (name "MOUSER PART NUMBER") "667-ERJ-2RKF1001X")
      )
      (libsource (lib "Project-SCH_Lib") (part "ERJ-2RKF1001X"))
    )
    (comp (ref "R31")
      (value "47.5K / 0603 / 1%")
      (footprint "Project-SCH_Lib:ERJ1GJJ2R4C")
      (description "Thick Film Resistors - SMD 0201 0.05W 1% 47.5KOhm AEC-Q200")
      (fields (field (name "MANUFACTURER_PART_NUMBER") "ERJ-1GJF4752C"))
      (libsource (lib "Project-SCH_Lib") (part "ERJ-1GJF4752C"))
    )
    (comp (ref "R32")
      (value "100k /1210/750mW")
      (footprint "Project-SCH_Lib:RESC3225X70N")
      (description "Resistor")
      (fields
        (field (name "MANUFACTURER_PART_NUMBER") "CRCW1210100KFKEAHP")
        (field (name "MOUSER PART NUMBER") "71-CRCW1210100KFKEAH")
      )
      (libsource (lib "Project-SCH_Lib") (part "CRCW1210100KFKEAHP"))
    )
    (comp (ref "R33")
      (value "10K / 0603 / 1%")
      (footprint "Project-SCH_Lib:ERJP03_PA3_(0603)")
      (description "Thick Film Resistors - SMD 0603 10Kohms 1% AEC-Q200")
      (fields
        (field (name "MANUFACTURER_PART_NUMBER") "ERJ-3EKF1002V")
        (field (name "MOUSER PART NUMBER") "667-ERJ-3EKF1002V")
      )
      (libsource (lib "Project-SCH_Lib") (part "ERJ-3EKF1002V"))
    )
    (comp (ref "R34")
      (value "3.3K (1W)")
      (footprint "Project-SCH_Lib:RESC2550X65N")
      (description "Resistor")
      (fields
        (field (name "MANUFACTURER_PART_NUMBER") "LTR50UZPF3301")
        (field (name "MOUSER PART NUMBER") "755-LTR50UZPF3301")
      )
      (libsource (lib "Project-SCH_Lib") (part "LTR50UZPF3301"))
    )
    (comp (ref "S1")
      (value "BUTTON")
      (footprint "Project-SCH_Lib:NTC013AT1JA160T")
      (description "Switch")
      (fields (field (name "MANUFACTURER_PART_NUMBER") "NTC013-AT1J-A160T"))
      (libsource (lib "Project-SCH_Lib") (part "NTC013-AT1J-A160T"))
    )
    (comp (ref "S2")
      (value "BUTTON")
      (footprint "Project-SCH_Lib:NTC013AT1JA160T")
      (description "Switch")
      (fields (field (name "MANUFACTURER_PART_NUMBER") "NTC013-AT1J-A160T"))
      (libsource (lib "Project-SCH_Lib") (part "NTC013-AT1J-A160T"))
    )
    (comp (ref "Y1")
      (value "3.6864 MHz")
      (footprint "Project-SCH_Lib:830030798")
      (description "Crystal or Oscillator")
      (fields
        (field (name "MANUFACTURER_PART_NUMBER") "830030798")
        (field (name "MOUSER PART NUMBER") "710-830030798")
      )
      (libsource (lib "Project-SCH_Lib") (part "830030798"))
    )
    (comp (ref "Z1")
      (value "PTZTFTE2515B")
      (footprint "PTZTFTE2515B")
      (description "Zener Diode")
      (fields (field (name "MOUSER PART NUMBER") "755-PTZTFTE2515B"))
      (libsource (lib "Project-SCH_Lib") (part "PTZTFTE2515B"))
    )
    (comp (ref "Z2")
      (value "PTZTFTE2515B")
      (footprint "PTZTFTE2515B")
      (description "Zener Diode")
      (fields (field (name "MOUSER PART NUMBER") "755-PTZTFTE2515B"))
      (libsource (lib "Project-SCH_Lib") (part "PTZTFTE2515B"))
    )
    (comp (ref "Z3")
      (value "PTZTFTE2515B")
      (footprint "PTZTFTE2515B")
      (description "Zener Diode")
      (fields (field (name "MOUSER PART NUMBER") "755-PTZTFTE2515B"))
      (libsource (lib "Project-SCH_Lib") (part "PTZTFTE2515B"))
    )
    (comp (ref "Z4")
      (value "PTZTFTE2515B")
      (footprint "PTZTFTE2515B")
      (description "Zener Diode")
      (fields (field (name "MOUSER PART NUMBER") "755-PTZTFTE2515B"))
      (libsource (lib "Project-SCH_Lib") (part "PTZTFTE2515B"))
    )
  )
  (nets
    (net (code "1") (name "/3.3V_REG_ISO") (class "Default")
      (node (ref "C23") (pin "2") (pinfunction "2_2") (pintype "passive"))
      (node (ref "C26") (pin "1") (pinfunction "1_1") (pintype "passive"))
      (node (ref "IC10") (pin "1") (pinfunction "IN_1") (pintype "passive"))
      (node (ref "IC10") (pin "3") (pinfunction "EN_3") (pintype "passive"))
      (node (ref "PS1") (pin "6") (pinfunction "+VOUT_6") (pintype "passive"))
    )
    (net (code "2") (name "/3V3-DIRTY") (class "Default")
      (node (ref "C22") (pin "1") (pinfunction "1_1") (pintype "passive"))
      (node (ref "C25") (pin "1") (pinfunction "1_1") (pintype "passive"))
      (node (ref "C27") (pin "1") (pinfunction "1_1") (pintype "passive"))
      (node (ref "IC10") (pin "5") (pinfunction "OUT_5") (pintype "passive"))
      (node (ref "IC11") (pin "8") (pinfunction "VDD_8") (pintype "power_in"))
      (node (ref "IC12") (pin "1") (pinfunction "VCC1_1") (pintype "passive"))
      (node (ref "IC5") (pin "8") (pinfunction "VDD_8") (pintype "power_in"))
      (node (ref "IC6") (pin "1") (pinfunction "VCC1_1") (pintype "passive"))
    )
    (net (code "3") (name "/3V3-REG") (class "Default")
      (node (ref "C16") (pin "1") (pinfunction "1_1") (pintype "passive"))
      (node (ref "C17") (pin "1") (pinfunction "1_1") (pintype "passive"))
      (node (ref "C2") (pin "1") (pinfunction "1_1") (pintype "passive"))
      (node (ref "C20") (pin "1") (pinfunction "1_1") (pintype "passive"))
      (node (ref "C24") (pin "1") (pinfunction "1_1") (pintype "passive"))
      (node (ref "C28") (pin "1") (pinfunction "1_1") (pintype "passive"))
      (node (ref "C3") (pin "1") (pinfunction "1_1") (pintype "passive"))
      (node (ref "C4") (pin "1") (pinfunction "1_1") (pintype "passive"))
      (node (ref "C5") (pin "1") (pinfunction "1_1") (pintype "passive"))
      (node (ref "IC1") (pin "1") (pinfunction "SPI/~{I2C}_1") (pintype "passive"))
      (node (ref "IC1") (pin "2") (pinfunction "LDOEN_2") (pintype "passive"))
      (node (ref "IC1") (pin "43") (pinfunction "VEXT_43") (pintype "passive"))
      (node (ref "IC1") (pin "47") (pinfunction "VA_47") (pintype "passive"))
      (node (ref "IC1") (pin "48") (pinfunction "V18_48") (pintype "passive"))
      (node (ref "IC1") (pin "9") (pinfunction "VL_9") (pintype "passive"))
      (node (ref "IC12") (pin "8") (pinfunction "VCC2_8") (pintype "passive"))
      (node (ref "IC4") (pin "2") (pinfunction "OUTPUT_1_2") (pintype "passive"))
      (node (ref "IC4") (pin "4") (pinfunction "OUTPUT_2_4") (pintype "passive"))
      (node (ref "IC6") (pin "8") (pinfunction "VCC2_8") (pintype "passive"))
      (node (ref "IC7") (pin "6") (pinfunction "VDD_6") (pintype "passive"))
      (node (ref "IC7") (pin "7") (pinfunction "VREGIN_7") (pintype "passive"))
      (node (ref "J11") (pin "5") (pinfunction "5_5") (pintype "passive"))
      (node (ref "J4") (pin "1") (pinfunction "1_1") (pintype "passive"))
      (node (ref "L2") (pin "1") (pinfunction "1_1") (pintype "passive"))
      (node (ref "R15") (pin "1") (pinfunction "1_1") (pintype "passive"))
      (node (ref "R18") (pin "1") (pinfunction "1_1") (pintype "passive"))
      (node (ref "R30") (pin "2") (pinfunction "2_2") (pintype "passive"))
      (node (ref "R33") (pin "2") (pinfunction "2_2") (pintype "passive"))
    )
    (net (code "4") (name "/5V-REG") (class "Default")
      (node (ref "C12") (pin "1") (pinfunction "1_1") (pintype "passive"))
      (node (ref "C13") (pin "1") (pinfunction "1_1") (pintype "passive"))
      (node (ref "C18") (pin "1") (pinfunction "1_1") (pintype "passive"))
      (node (ref "C19") (pin "1") (pinfunction "1_1") (pintype "passive"))
      (node (ref "D10") (pin "1") (pinfunction "K_1") (pintype "passive"))
      (node (ref "IC4") (pin "3") (pinfunction "INPUT_3") (pintype "passive"))
      (node (ref "J8") (pin "1") (pinfunction "1_1") (pintype "passive"))
      (node (ref "K1") (pin "1") (pinfunction "COIL_1_1") (pintype "passive"))
      (node (ref "K2") (pin "1") (pinfunction "COIL_1_1") (pintype "passive"))
      (node (ref "K3") (pin "1") (pinfunction "COIL_1_1") (pintype "passive"))
      (node (ref "L1") (pin "2") (pinfunction "2_2") (pintype "passive"))
      (node (ref "L1") (pin "4") (pinfunction "4_4") (pintype "passive"))
      (node (ref "R13") (pin "2") (pinfunction "2_2") (pintype "passive"))
      (node (ref "Z1") (pin "1") (pinfunction "C_1") (pintype "passive"))
      (node (ref "Z3") (pin "1") (pinfunction "C_1") (pintype "passive"))
      (node (ref "Z4") (pin "1") (pinfunction "C_1") (pintype "passive"))
    )
    (net (code "5") (name "/12V") (class "Default")
      (node (ref "C8") (pin "1") (pinfunction "1_1") (pintype "passive"))
      (node (ref "F2") (pin "1") (pinfunction "1_1") (pintype "passive"))
      (node (ref "FL2") (pin "2") (pinfunction "2_2") (pintype "passive"))
    )
    (net (code "6") (name "/12V-PROT") (class "Default")
      (node (ref "C11") (pin "1") (pinfunction "1_1") (pintype "passive"))
      (node (ref "C14") (pin "1") (pinfunction "1_1") (pintype "passive"))
      (node (ref "D1") (pin "1") (pinfunction "K_1") (pintype "passive"))
      (node (ref "F1") (pin "2") (pinfunction "2_2") (pintype "passive"))
      (node (ref "IC2") (pin "11") (pinfunction "VIN_2_11") (pintype "passive"))
      (node (ref "IC2") (pin "3") (pinfunction "EN/UVLO_3") (pintype "passive"))
      (node (ref "IC2") (pin "4") (pinfunction "VIN_1_4") (pintype "passive"))
      (node (ref "Q2") (pin "2") (pinfunction "D_2") (pintype "passive"))
    )
    (net (code "7") (name "/12V_FUSE") (class "Default")
      (node (ref "F1") (pin "1") (pinfunction "1_1") (pintype "passive"))
      (node (ref "J2") (pin "1") (pinfunction "1_1") (pintype "output"))
    )
    (net (code "8") (name "/AUX-N") (class "Default")
      (node (ref "IC11") (pin "5") (pinfunction "AIN1_5") (pintype "input"))
      (node (ref "J15") (pin "2") (pinfunction "2_2") (pintype "output"))
      (node (ref "R32") (pin "2") (pinfunction "2_2") (pintype "passive"))
    )
    (net (code "9") (name "/AUX-P") (class "Default")
      (node (ref "IC11") (pin "4") (pinfunction "AIN0_4") (pintype "input"))
      (node (ref "R28") (pin "2") (pinfunction "2_2") (pintype "passive"))
      (node (ref "R32") (pin "1") (pinfunction "1_1") (pintype "passive"))
    )
    (net (code "10") (name "/BAT-N") (class "Default")
      (node (ref "IC5") (pin "5") (pinfunction "AIN1_5") (pintype "input"))
      (node (ref "J14") (pin "2") (pinfunction "2_2") (pintype "output"))
      (node (ref "R23") (pin "2") (pinfunction "2_2") (pintype "passive"))
    )
    (net (code "11") (name "/BAT-P") (class "Default")
      (node (ref "IC5") (pin "4") (pinfunction "AIN0_4") (pintype "input"))
      (node (ref "R22") (pin "2") (pinfunction "2_2") (pintype "passive"))
      (node (ref "R23") (pin "1") (pinfunction "1_1") (pintype "passive"))
    )
    (net (code "12") (name "/CHIP_PU") (class "Default")
      (node (ref "C21") (pin "1") (pinfunction "1_1") (pintype "passive"))
      (node (ref "C31") (pin "1") (pinfunction "1_1") (pintype "passive"))
      (node (ref "IC3") (pin "3") (pinfunction "EN_3") (pintype "passive"))
      (node (ref "R18") (pin "2") (pinfunction "2_2") (pintype "passive"))
      (node (ref "R25") (pin "2") (pinfunction "2_2") (pintype "passive"))
      (node (ref "S2") (pin "3") (pinfunction "COM_1_3") (pintype "passive"))
    )
    (net (code "13") (name "/CLK") (class "Default")
      (node (ref "IC1") (pin "4") (pinfunction "SCLK/SCL_4") (pintype "passive"))
      (node (ref "IC3") (pin "20") (pinfunction "IO12_20") (pintype "passive"))
    )
    (net (code "14") (name "/CS") (class "Default")
      (node (ref "IC1") (pin "5") (pinfunction "~{CS}/A0_5") (pintype "passive"))
      (node (ref "IC3") (pin "18") (pinfunction "IO10_18") (pintype "passive"))
    )
    (net (code "15") (name "/DTR") (class "Default")
      (node (ref "IC7") (pin "28") (pinfunction "DTR_28") (pintype "passive"))
      (node (ref "IC9") (pin "2") (pinfunction "E_2") (pintype "passive"))
      (node (ref "R24") (pin "1") (pinfunction "1_1") (pintype "passive"))
    )
    (net (code "16") (name "/ESP_RXD") (class "Default")
      (node (ref "IC3") (pin "36") (pinfunction "RXD0_36") (pintype "passive"))
      (node (ref "IC7") (pin "26") (pinfunction "TXD_26") (pintype "passive"))
    )
    (net (code "17") (name "/ESP_TXD") (class "Default")
      (node (ref "IC3") (pin "37") (pinfunction "TXD0_37") (pintype "passive"))
      (node (ref "IC7") (pin "25") (pinfunction "RXD_25") (pintype "passive"))
    )
    (net (code "18") (name "/GND_1") (class "Default")
      (node (ref "D1") (pin "2") (pinfunction "A_1_2") (pintype "passive"))
      (node (ref "D1") (pin "3") (pinfunction "A_2_3") (pintype "passive"))
      (node (ref "FL1") (pin "2") (pinfunction "2_2") (pintype "passive"))
      (node (ref "J2") (pin "2") (pinfunction "2_2") (pintype "output"))
      (node (ref "R9") (pin "1") (pinfunction "1_1") (pintype "passive"))
    )
    (net (code "19") (name "/GND_2") (class "Default")
      (node (ref "C1") (pin "2") (pinfunction "2_2") (pintype "passive"))
      (node (ref "C11") (pin "2") (pinfunction "2_2") (pintype "passive"))
      (node (ref "C12") (pin "2") (pinfunction "2_2") (pintype "passive"))
      (node (ref "C13") (pin "2") (pinfunction "2_2") (pintype "passive"))
      (node (ref "C14") (pin "2") (pinfunction "2_2") (pintype "passive"))
      (node (ref "C15") (pin "2") (pinfunction "2_2") (pintype "passive"))
      (node (ref "C16") (pin "2") (pinfunction "2_2") (pintype "passive"))
      (node (ref "C17") (pin "2") (pinfunction "2_2") (pintype "passive"))
      (node (ref "C18") (pin "2") (pinfunction "2_2") (pintype "passive"))
      (node (ref "C19") (pin "2") (pinfunction "2_2") (pintype "passive"))
      (node (ref "C2") (pin "2") (pinfunction "2_2") (pintype "passive"))
      (node (ref "C20") (pin "2") (pinfunction "2_2") (pintype "passive"))
      (node (ref "C21") (pin "2") (pinfunction "2_2") (pintype "passive"))
      (node (ref "C24") (pin "2") (pinfunction "2_2") (pintype "passive"))
      (node (ref "C28") (pin "2") (pinfunction "2_2") (pintype "passive"))
      (node (ref "C29") (pin "2") (pinfunction "2_2") (pintype "passive"))
      (node (ref "C3") (pin "2") (pinfunction "2_2") (pintype "passive"))
      (node (ref "C30") (pin "1") (pinfunction "1_1") (pintype "passive"))
      (node (ref "C31") (pin "2") (pinfunction "2_2") (pintype "passive"))
      (node (ref "C32") (pin "2") (pinfunction "2_2") (pintype "passive"))
      (node (ref "C4") (pin "2") (pinfunction "2_2") (pintype "passive"))
      (node (ref "C5") (pin "2") (pinfunction "2_2") (pintype "passive"))
      (node (ref "C6") (pin "2") (pinfunction "2_2") (pintype "passive"))
      (node (ref "C7") (pin "2") (pinfunction "2_2") (pintype "passive"))
      (node (ref "C8") (pin "2") (pinfunction "2_2") (pintype "passive"))
      (node (ref "C9") (pin "2") (pinfunction "2_2") (pintype "passive"))
      (node (ref "D11") (pin "2") (pinfunction "2_2") (pintype "passive"))
      (node (ref "D12") (pin "2") (pinfunction "2_2") (pintype "passive"))
      (node (ref "D13") (pin "2") (pinfunction "2_2") (pintype "passive"))
      (node (ref "D2") (pin "2") (pinfunction "A_2") (pintype "passive"))
      (node (ref "D3") (pin "2") (pinfunction "A_2") (pintype "passive"))
      (node (ref "D4") (pin "2") (pinfunction "A_2") (pintype "passive"))
      (node (ref "D7") (pin "2") (pinfunction "A_2") (pintype "passive"))
      (node (ref "D9") (pin "2") (pinfunction "A_2") (pintype "passive"))
      (node (ref "FL1") (pin "3") (pinfunction "3_3") (pintype "passive"))
      (node (ref "IC1") (pin "10") (pinfunction "DGND_10") (pintype "passive"))
      (node (ref "IC12") (pin "5") (pinfunction "GND2_5") (pintype "passive"))
      (node (ref "IC2") (pin "1") (pinfunction "MODE/SYNC_1_1") (pintype "passive"))
      (node (ref "IC2") (pin "10") (pinfunction "MODE/SYNC_2_10") (pintype "passive"))
      (node (ref "IC2") (pin "9") (pinfunction "GND_9") (pintype "passive"))
      (node (ref "IC3") (pin "1") (pinfunction "GND_1_1") (pintype "passive"))
      (node (ref "IC3") (pin "40") (pinfunction "GND_2_40") (pintype "passive"))
      (node (ref "IC3") (pin "41") (pinfunction "GND_3_41") (pintype "passive"))
      (node (ref "IC3") (pin "42") (pinfunction "GND_4_42") (pintype "passive"))
      (node (ref "IC3") (pin "43") (pinfunction "GND_5_43") (pintype "passive"))
      (node (ref "IC3") (pin "44") (pinfunction "GND_6_44") (pintype "passive"))
      (node (ref "IC3") (pin "45") (pinfunction "GND_7_45") (pintype "passive"))
      (node (ref "IC3") (pin "46") (pinfunction "GND_8_46") (pintype "passive"))
      (node (ref "IC3") (pin "47") (pinfunction "GND_9_47") (pintype "passive"))
      (node (ref "IC3") (pin "48") (pinfunction "GND_10_48") (pintype "passive"))
      (node (ref "IC3") (pin "49") (pinfunction "GND_11_49") (pintype "passive"))
      (node (ref "IC4") (pin "1") (pinfunction "GROUND_1") (pintype "passive"))
      (node (ref "IC6") (pin "5") (pinfunction "GND2_5") (pintype "passive"))
      (node (ref "IC7") (pin "11") (pinfunction "SUSPENDB_11") (pintype "passive"))
      (node (ref "IC7") (pin "29") (pinfunction "GND_2_29") (pintype "passive"))
      (node (ref "IC7") (pin "3") (pinfunction "GND_1_3") (pintype "passive"))
      (node (ref "J1") (pin "1") (pinfunction "GND_1") (pintype "passive"))
      (node (ref "J11") (pin "2") (pinfunction "2_2") (pintype "passive"))
      (node (ref "J13") (pin "2") (pinfunction "2_2") (pintype "passive"))
      (node (ref "J16") (pin "2") (pinfunction "2_2") (pintype "output"))
      (node (ref "J19") (pin "A1") (pinfunction "GND_1_A1") (pintype "passive"))
      (node (ref "J19") (pin "A12") (pinfunction "GND_2_A12") (pintype "passive"))
      (node (ref "J19") (pin "B1") (pinfunction "GND_3_B1") (pintype "passive"))
      (node (ref "J19") (pin "B12") (pinfunction "GND_4_B12") (pintype "passive"))
      (node (ref "J4") (pin "11") (pinfunction "11_11") (pintype "passive"))
      (node (ref "J4") (pin "12") (pinfunction "12_12") (pintype "passive"))
      (node (ref "J4") (pin "2") (pinfunction "2_2") (pintype "passive"))
      (node (ref "J6") (pin "1") (pinfunction "GND_1") (pintype "passive"))
      (node (ref "J7") (pin "1") (pinfunction "GND_1") (pintype "passive"))
      (node (ref "J8") (pin "11") (pinfunction "11_11") (pintype "passive"))
      (node (ref "J8") (pin "12") (pinfunction "12_12") (pintype "passive"))
      (node (ref "J8") (pin "2") (pinfunction "2_2") (pintype "passive"))
      (node (ref "J9") (pin "1") (pinfunction "GND_1") (pintype "passive"))
      (node (ref "LED1") (pin "3") (pinfunction "K_GREEN_3") (pintype "passive"))
      (node (ref "LED1") (pin "4") (pinfunction "K_RED_4") (pintype "passive"))
      (node (ref "LED2") (pin "3") (pinfunction "K_GREEN_3") (pintype "passive"))
      (node (ref "LED2") (pin "4") (pinfunction "K_RED_4") (pintype "passive"))
      (node (ref "LED3") (pin "3") (pinfunction "K_GREEN_3") (pintype "passive"))
      (node (ref "LED3") (pin "4") (pinfunction "K_RED_4") (pintype "passive"))
      (node (ref "PS1") (pin "2") (pinfunction "-VIN_2") (pintype "input"))
      (node (ref "Q1") (pin "2") (pinfunction "E_2") (pintype "passive"))
      (node (ref "Q3") (pin "2") (pinfunction "E_2") (pintype "passive"))
      (node (ref "Q4") (pin "2") (pinfunction "E_2") (pintype "passive"))
      (node (ref "Q5") (pin "2") (pinfunction "K_2") (pintype "passive"))
      (node (ref "Q5") (pin "3") (pinfunction "E_3") (pintype "passive"))
      (node (ref "R12") (pin "1") (pinfunction "1_1") (pintype "passive"))
      (node (ref "R2") (pin "1") (pinfunction "1_1") (pintype "passive"))
      (node (ref "R31") (pin "2") (pinfunction "2_2") (pintype "passive"))
      (node (ref "R4") (pin "1") (pinfunction "1_1") (pintype "passive"))
      (node (ref "R7") (pin "1") (pinfunction "1_1") (pintype "passive"))
      (node (ref "S1") (pin "1") (pinfunction "NO_1_1") (pintype "passive"))
      (node (ref "S2") (pin "1") (pinfunction "NO_1_1") (pintype "passive"))
    )
    (net (code "20") (name "/GND_3") (class "Default")
      (node (ref "C22") (pin "2") (pinfunction "2_2") (pintype "passive"))
      (node (ref "C25") (pin "2") (pinfunction "2_2") (pintype "passive"))
      (node (ref "C26") (pin "2") (pinfunction "2_2") (pintype "passive"))
      (node (ref "C27") (pin "2") (pinfunction "2_2") (pintype "passive"))
      (node (ref "C30") (pin "2") (pinfunction "2_2") (pintype "passive"))
      (node (ref "IC10") (pin "2") (pinfunction "GND_2") (pintype "passive"))
      (node (ref "IC10") (pin "4") (pinfunction "NC_4") (pintype "passive"))
      (node (ref "IC11") (pin "1") (pinfunction "ADDR_1") (pintype "passive"))
      (node (ref "IC11") (pin "3") (pinfunction "GND_3") (pintype "power_in"))
      (node (ref "IC12") (pin "4") (pinfunction "GND1_4") (pintype "passive"))
      (node (ref "IC5") (pin "1") (pinfunction "ADDR_1") (pintype "passive"))
      (node (ref "IC5") (pin "3") (pinfunction "GND_3") (pintype "power_in"))
      (node (ref "IC6") (pin "4") (pinfunction "GND1_4") (pintype "passive"))
      (node (ref "PS1") (pin "5") (pinfunction "-VOUT_5") (pintype "passive"))
    )
    (net (code "21") (name "/GPIO_0") (class "Default")
      (node (ref "C32") (pin "1") (pinfunction "1_1") (pintype "passive"))
      (node (ref "R27") (pin "2") (pinfunction "2_2") (pintype "passive"))
      (node (ref "S1") (pin "3") (pinfunction "COM_1_3") (pintype "passive"))
    )
    (net (code "22") (name "/GPIO_35") (class "Default")
      (node (ref "IC3") (pin "28") (pinfunction "IO35_28") (pintype "passive"))
      (node (ref "R8") (pin "1") (pinfunction "1_1") (pintype "passive"))
    )
    (net (code "23") (name "/GPIO_36") (class "Default")
      (node (ref "IC3") (pin "29") (pinfunction "IO36_29") (pintype "passive"))
      (node (ref "R10") (pin "1") (pinfunction "1_1") (pintype "passive"))
    )
    (net (code "24") (name "/GPIO_37") (class "Default")
      (node (ref "IC3") (pin "30") (pinfunction "IO37_30") (pintype "passive"))
      (node (ref "R16") (pin "1") (pinfunction "1_1") (pintype "passive"))
    )
    (net (code "25") (name "/GPIO_38") (class "Default")
      (node (ref "IC3") (pin "31") (pinfunction "IO38_31") (pintype "passive"))
      (node (ref "R17") (pin "1") (pinfunction "1_1") (pintype "passive"))
    )
    (net (code "26") (name "/GPIO_39") (class "Default")
      (node (ref "IC3") (pin "32") (pinfunction "IO39_32") (pintype "passive"))
      (node (ref "R20") (pin "1") (pinfunction "1_1") (pintype "passive"))
    )
    (net (code "27") (name "/GPIO_40") (class "Default")
      (node (ref "IC3") (pin "33") (pinfunction "IO40_33") (pintype "passive"))
      (node (ref "R21") (pin "1") (pinfunction "1_1") (pintype "passive"))
    )
    (net (code "28") (name "/GPIO_41") (class "Default")
      (node (ref "IC3") (pin "34") (pinfunction "IO41_34") (pintype "passive"))
      (node (ref "R5") (pin "1") (pinfunction "1_1") (pintype "passive"))
    )
    (net (code "29") (name "/GPIO_42") (class "Default")
      (node (ref "IC3") (pin "35") (pinfunction "IO42_35") (pintype "passive"))
      (node (ref "R14") (pin "1") (pinfunction "1_1") (pintype "passive"))
    )
    (net (code "30") (name "/GPIO_45") (class "Default")
      (node (ref "IC3") (pin "26") (pinfunction "IO45_26") (pintype "passive"))
      (node (ref "R19") (pin "1") (pinfunction "1_1") (pintype "passive"))
    )
    (net (code "31") (name "/IO0") (class "Default")
      (node (ref "IC3") (pin "27") (pinfunction "IO0_27") (pintype "passive"))
      (node (ref "J4") (pin "3") (pinfunction "3_3") (pintype "passive"))
    )
    (net (code "32") (name "/IO1") (class "Default")
      (node (ref "IC3") (pin "39") (pinfunction "IO1_39") (pintype "passive"))
      (node (ref "Q5") (pin "4") (pinfunction "C_4") (pintype "passive"))
      (node (ref "R33") (pin "1") (pinfunction "1_1") (pintype "passive"))
    )
    (net (code "33") (name "/IO2") (class "Default")
      (node (ref "IC3") (pin "38") (pinfunction "IO2_38") (pintype "passive"))
      (node (ref "J4") (pin "4") (pinfunction "4_4") (pintype "passive"))
    )
    (net (code "34") (name "/IO3") (class "Default")
      (node (ref "IC3") (pin "15") (pinfunction "IO3_15") (pintype "passive"))
      (node (ref "J4") (pin "5") (pinfunction "5_5") (pintype "passive"))
    )
    (net (code "35") (name "/IO6") (class "Default")
      (node (ref "IC3") (pin "6") (pinfunction "IO6_6") (pintype "passive"))
      (node (ref "J4") (pin "6") (pinfunction "6_6") (pintype "passive"))
    )
    (net (code "36") (name "/IO7") (class "Default")
      (node (ref "IC3") (pin "7") (pinfunction "IO7_7") (pintype "passive"))
      (node (ref "J4") (pin "7") (pinfunction "7_7") (pintype "passive"))
    )
    (net (code "37") (name "/IO14") (class "Default")
      (node (ref "IC3") (pin "22") (pinfunction "IO14_22") (pintype "passive"))
      (node (ref "J4") (pin "8") (pinfunction "8_8") (pintype "passive"))
    )
    (net (code "38") (name "/IO15") (class "Default")
      (node (ref "IC3") (pin "8") (pinfunction "IO15_8") (pintype "passive"))
      (node (ref "J4") (pin "9") (pinfunction "9_9") (pintype "passive"))
    )
    (net (code "39") (name "/IO16") (class "Default")
      (node (ref "IC3") (pin "9") (pinfunction "IO16_9") (pintype "passive"))
      (node (ref "J4") (pin "10") (pinfunction "10_10") (pintype "passive"))
    )
    (net (code "40") (name "/IO17") (class "Default")
      (node (ref "IC3") (pin "10") (pinfunction "IO17_10") (pintype "passive"))
      (node (ref "J11") (pin "4") (pinfunction "4_4") (pintype "passive"))
    )
    (net (code "41") (name "/IO18") (class "Default")
      (node (ref "IC3") (pin "11") (pinfunction "IO18_11") (pintype "passive"))
      (node (ref "J11") (pin "3") (pinfunction "3_3") (pintype "passive"))
    )
    (net (code "42") (name "/IO19") (class "Default")
      (node (ref "IC3") (pin "13") (pinfunction "IO19_13") (pintype "passive"))
      (node (ref "J8") (pin "5") (pinfunction "5_5") (pintype "passive"))
    )
    (net (code "43") (name "/IO20") (class "Default")
      (node (ref "IC3") (pin "14") (pinfunction "IO20_14") (pintype "passive"))
      (node (ref "J8") (pin "6") (pinfunction "6_6") (pintype "passive"))
    )
    (net (code "44") (name "/IO21") (class "Default")
      (node (ref "IC3") (pin "23") (pinfunction "IO21_23") (pintype "passive"))
      (node (ref "J8") (pin "7") (pinfunction "7_7") (pintype "passive"))
    )
    (net (code "45") (name "/IO46") (class "Default")
      (node (ref "IC3") (pin "16") (pinfunction "IO46_16") (pintype "passive"))
      (node (ref "J8") (pin "8") (pinfunction "8_8") (pintype "passive"))
    )
    (net (code "46") (name "/IO47") (class "Default")
      (node (ref "IC3") (pin "24") (pinfunction "IO47_24") (pintype "passive"))
      (node (ref "J8") (pin "9") (pinfunction "9_9") (pintype "passive"))
    )
    (net (code "47") (name "/IO48") (class "Default")
      (node (ref "IC3") (pin "25") (pinfunction "IO48_25") (pintype "passive"))
      (node (ref "J8") (pin "10") (pinfunction "10_10") (pintype "passive"))
    )
    (net (code "48") (name "/MISO") (class "Default")
      (node (ref "IC1") (pin "3") (pinfunction "MISO/SDA_3") (pintype "passive"))
      (node (ref "IC3") (pin "21") (pinfunction "IO13_21") (pintype "passive"))
    )
    (net (code "49") (name "/MOSI") (class "Default")
      (node (ref "IC1") (pin "6") (pinfunction "MOSI/A1_6") (pintype "passive"))
      (node (ref "IC3") (pin "19") (pinfunction "IO11_19") (pintype "passive"))
    )
    (net (code "50") (name "/RTS") (class "Default")
      (node (ref "IC7") (pin "24") (pinfunction "RTS_24") (pintype "passive"))
      (node (ref "IC8") (pin "2") (pinfunction "E_2") (pintype "passive"))
      (node (ref "R26") (pin "1") (pinfunction "1_1") (pintype "passive"))
    )
    (net (code "51") (name "/SCL_AUX") (class "Default")
      (node (ref "IC12") (pin "6") (pinfunction "SCL2_6") (pintype "passive"))
      (node (ref "IC3") (pin "17") (pinfunction "IO9_17") (pintype "passive"))
    )
    (net (code "52") (name "/SCL_BAT") (class "Default")
      (node (ref "IC3") (pin "5") (pinfunction "IO5_5") (pintype "passive"))
      (node (ref "IC6") (pin "6") (pinfunction "SCL2_6") (pintype "passive"))
    )
    (net (code "53") (name "/SDA_AUX") (class "Default")
      (node (ref "IC12") (pin "7") (pinfunction "SDA2_7") (pintype "passive"))
      (node (ref "IC3") (pin "12") (pinfunction "IO8_12") (pintype "passive"))
    )
    (net (code "54") (name "/SDA_BAT") (class "Default")
      (node (ref "IC3") (pin "4") (pinfunction "IO4_4") (pintype "passive"))
      (node (ref "IC6") (pin "7") (pinfunction "SDA2_7") (pintype "passive"))
    )
    (net (code "55") (name "/USB_D_N") (class "Default")
      (node (ref "D11") (pin "1") (pinfunction "1_1") (pintype "passive"))
      (node (ref "IC7") (pin "5") (pinfunction "D-_5") (pintype "passive"))
      (node (ref "J19") (pin "A7") (pinfunction "DN1_A7") (pintype "passive"))
      (node (ref "J19") (pin "B7") (pinfunction "DN2_B7") (pintype "passive"))
    )
    (net (code "56") (name "/USB_D_P") (class "Default")
      (node (ref "D12") (pin "1") (pinfunction "1_1") (pintype "passive"))
      (node (ref "IC7") (pin "4") (pinfunction "D+_4") (pintype "passive"))
      (node (ref "J19") (pin "A6") (pinfunction "DP1_A6") (pintype "passive"))
      (node (ref "J19") (pin "B6") (pinfunction "DP2_B6") (pintype "passive"))
    )
    (net (code "57") (name "/VBUS") (class "Default")
      (node (ref "D10") (pin "2") (pinfunction "A_2") (pintype "passive"))
      (node (ref "D13") (pin "1") (pinfunction "1_1") (pintype "passive"))
      (node (ref "J19") (pin "A4") (pinfunction "VBUS_1_A4") (pintype "passive"))
      (node (ref "J19") (pin "A9") (pinfunction "VBUS_2_A9") (pintype "passive"))
      (node (ref "J19") (pin "B4") (pinfunction "VBUS_3_B4") (pintype "passive"))
      (node (ref "R29") (pin "1") (pinfunction "1_1") (pintype "passive"))
    )
    (net (code "58") (name "/VE_TX_0") (class "Default")
      (node (ref "IC1") (pin "17") (pinfunction "RX0_17") (pintype "passive"))
      (node (ref "J3") (pin "3") (pinfunction "3_3") (pintype "passive"))
      (node (ref "R1") (pin "2") (pinfunction "2_2") (pintype "passive"))
      (node (ref "R2") (pin "2") (pinfunction "2_2") (pintype "passive"))
    )
    (net (code "59") (name "/VE_TX_1") (class "Default")
      (node (ref "IC1") (pin "25") (pinfunction "RX1_25") (pintype "passive"))
      (node (ref "J12") (pin "3") (pinfunction "3_3") (pintype "passive"))
      (node (ref "R3") (pin "2") (pinfunction "2_2") (pintype "passive"))
      (node (ref "R4") (pin "2") (pinfunction "2_2") (pintype "passive"))
    )
    (net (code "60") (name "/VE_TX_2") (class "Default")
      (node (ref "IC1") (pin "33") (pinfunction "RX2_33") (pintype "passive"))
      (node (ref "J17") (pin "3") (pinfunction "3_3") (pintype "passive"))
      (node (ref "R6") (pin "2") (pinfunction "2_2") (pintype "passive"))
      (node (ref "R7") (pin "2") (pinfunction "2_2") (pintype "passive"))
    )
    (net (code "61") (name "/VE_TX_3") (class "Default")
      (node (ref "IC1") (pin "41") (pinfunction "RX3_41") (pintype "passive"))
      (node (ref "J18") (pin "3") (pinfunction "3_3") (pintype "passive"))
      (node (ref "R11") (pin "2") (pinfunction "2_2") (pintype "passive"))
      (node (ref "R12") (pin "2") (pinfunction "2_2") (pintype "passive"))
    )
    (net (code "62") (name "/XIN") (class "Default")
      (node (ref "C1") (pin "1") (pinfunction "1_1") (pintype "passive"))
      (node (ref "IC1") (pin "45") (pinfunction "XIN_45") (pintype "passive"))
      (node (ref "Y1") (pin "2") (pinfunction "2_2") (pintype "passive"))
    )
    (net (code "63") (name "/XOUT") (class "Default")
      (node (ref "C6") (pin "1") (pinfunction "1_1") (pintype "passive"))
      (node (ref "IC1") (pin "44") (pinfunction "XOUT_44") (pintype "passive"))
      (node (ref "Y1") (pin "1") (pinfunction "1_1") (pintype "passive"))
    )
    (net (code "64") (name "Net-(C7-Pad1)") (class "Default")
      (node (ref "C7") (pin "1") (pinfunction "1_1") (pintype "passive"))
      (node (ref "C9") (pin "1") (pinfunction "1_1") (pintype "passive"))
      (node (ref "FL1") (pin "4") (pinfunction "4_4") (pintype "passive"))
      (node (ref "FL2") (pin "1") (pinfunction "1_1") (pintype "passive"))
    )
    (net (code "65") (name "Net-(D2-K)") (class "Default")
      (node (ref "D2") (pin "1") (pinfunction "K_1") (pintype "passive"))
      (node (ref "J12") (pin "2") (pinfunction "2_2") (pintype "passive"))
      (node (ref "J6") (pin "3") (pinfunction "TX_3") (pintype "passive"))
    )
    (net (code "66") (name "Net-(D3-K)") (class "Default")
      (node (ref "D3") (pin "1") (pinfunction "K_1") (pintype "passive"))
      (node (ref "Q5") (pin "1") (pinfunction "A_1") (pintype "passive"))
      (node (ref "R34") (pin "2") (pinfunction "2_2") (pintype "passive"))
    )
    (net (code "67") (name "Net-(D4-K)") (class "Default")
      (node (ref "D4") (pin "1") (pinfunction "K_1") (pintype "passive"))
      (node (ref "J1") (pin "3") (pinfunction "TX_3") (pintype "passive"))
      (node (ref "J3") (pin "2") (pinfunction "2_2") (pintype "passive"))
    )
    (net (code "68") (name "Net-(D7-K)") (class "Default")
      (node (ref "D7") (pin "1") (pinfunction "K_1") (pintype "passive"))
      (node (ref "J18") (pin "2") (pinfunction "2_2") (pintype "passive"))
      (node (ref "J9") (pin "3") (pinfunction "TX_3") (pintype "passive"))
    )
    (net (code "69") (name "Net-(D9-K)") (class "Default")
      (node (ref "D9") (pin "1") (pinfunction "K_1") (pintype "passive"))
      (node (ref "J17") (pin "2") (pinfunction "2_2") (pintype "passive"))
      (node (ref "J7") (pin "3") (pinfunction "TX_3") (pintype "passive"))
    )
    (net (code "70") (name "Net-(IC2-BOOT)") (class "Default")
      (node (ref "C10") (pin "1") (pinfunction "1_1") (pintype "passive"))
      (node (ref "IC2") (pin "6") (pinfunction "BOOT_6") (pintype "passive"))
    )
    (net (code "71") (name "Net-(IC2-SW_1)") (class "Default")
      (node (ref "C10") (pin "2") (pinfunction "2_2") (pintype "passive"))
      (node (ref "IC2") (pin "12") (pinfunction "SW_2_12") (pintype "passive"))
      (node (ref "IC2") (pin "5") (pinfunction "SW_1_5") (pintype "passive"))
      (node (ref "L1") (pin "1") (pinfunction "1_1") (pintype "passive"))
      (node (ref "L1") (pin "3") (pinfunction "3_3") (pintype "passive"))
    )
    (net (code "72") (name "Net-(IC2-VCC)") (class "Default")
      (node (ref "C15") (pin "1") (pinfunction "1_1") (pintype "passive"))
      (node (ref "IC2") (pin "7") (pinfunction "VCC_7") (pintype "passive"))
    )
    (net (code "73") (name "Net-(IC2-VOUT{slash}FB_1)") (class "Default")
      (node (ref "IC2") (pin "13") (pinfunction "VOUT/FB_2_13") (pintype "passive"))
      (node (ref "IC2") (pin "8") (pinfunction "VOUT/FB_1_8") (pintype "passive"))
      (node (ref "R13") (pin "1") (pinfunction "1_1") (pintype "passive"))
    )
    (net (code "74") (name "Net-(IC3-3V3)") (class "Default")
      (node (ref "IC3") (pin "2") (pinfunction "3V3_2") (pintype "passive"))
      (node (ref "R15") (pin "2") (pinfunction "2_2") (pintype "passive"))
    )
    (net (code "75") (name "Net-(IC5-SCL)") (class "Default")
      (node (ref "IC5") (pin "10") (pinfunction "SCL_10") (pintype "passive"))
      (node (ref "IC6") (pin "2") (pinfunction "SDA1_2") (pintype "passive"))
    )
    (net (code "76") (name "Net-(IC5-SDA)") (class "Default")
      (node (ref "IC5") (pin "9") (pinfunction "SDA_9") (pintype "passive"))
      (node (ref "IC6") (pin "3") (pinfunction "SCL1_3") (pintype "passive"))
    )
    (net (code "77") (name "Net-(IC7-RSTB)") (class "Default")
      (node (ref "IC7") (pin "9") (pinfunction "RSTB_9") (pintype "passive"))
      (node (ref "R30") (pin "1") (pinfunction "1_1") (pintype "passive"))
    )
    (net (code "78") (name "Net-(IC7-VBUS)") (class "Default")
      (node (ref "C29") (pin "1") (pinfunction "1_1") (pintype "passive"))
      (node (ref "IC7") (pin "8") (pinfunction "VBUS_8") (pintype "passive"))
      (node (ref "R29") (pin "2") (pinfunction "2_2") (pintype "passive"))
      (node (ref "R31") (pin "1") (pinfunction "1_1") (pintype "passive"))
    )
    (net (code "79") (name "Net-(IC8-B)") (class "Default")
      (node (ref "IC8") (pin "1") (pinfunction "B_1") (pintype "passive"))
      (node (ref "R24") (pin "2") (pinfunction "2_2") (pintype "passive"))
    )
    (net (code "80") (name "Net-(IC8-C)") (class "Default")
      (node (ref "IC8") (pin "3") (pinfunction "C_3") (pintype "passive"))
      (node (ref "R25") (pin "1") (pinfunction "1_1") (pintype "passive"))
    )
    (net (code "81") (name "Net-(IC9-B)") (class "Default")
      (node (ref "IC9") (pin "1") (pinfunction "B_1") (pintype "passive"))
      (node (ref "R26") (pin "2") (pinfunction "2_2") (pintype "passive"))
    )
    (net (code "82") (name "Net-(IC9-C)") (class "Default")
      (node (ref "IC9") (pin "3") (pinfunction "C_3") (pintype "passive"))
      (node (ref "R27") (pin "1") (pinfunction "1_1") (pintype "passive"))
    )
    (net (code "83") (name "Net-(IC11-SCL)") (class "Default")
      (node (ref "IC11") (pin "10") (pinfunction "SCL_10") (pintype "passive"))
      (node (ref "IC12") (pin "2") (pinfunction "SDA1_2") (pintype "passive"))
    )
    (net (code "84") (name "Net-(IC11-SDA)") (class "Default")
      (node (ref "IC11") (pin "9") (pinfunction "SDA_9") (pintype "passive"))
      (node (ref "IC12") (pin "3") (pinfunction "SCL1_3") (pintype "passive"))
    )
    (net (code "85") (name "Net-(J3-Pad1)") (class "Default")
      (node (ref "J3") (pin "1") (pinfunction "1_1") (pintype "passive"))
      (node (ref "R1") (pin "1") (pinfunction "1_1") (pintype "passive"))
    )
    (net (code "86") (name "Net-(J12-Pad1)") (class "Default")
      (node (ref "J12") (pin "1") (pinfunction "1_1") (pintype "passive"))
      (node (ref "R3") (pin "1") (pinfunction "1_1") (pintype "passive"))
    )
    (net (code "87") (name "Net-(J14-Pad1)") (class "Default")
      (node (ref "J14") (pin "1") (pinfunction "1_1") (pintype "output"))
      (node (ref "R22") (pin "1") (pinfunction "1_1") (pintype "passive"))
    )
    (net (code "88") (name "Net-(J15-Pad1)") (class "Default")
      (node (ref "J15") (pin "1") (pinfunction "1_1") (pintype "output"))
      (node (ref "R28") (pin "1") (pinfunction "1_1") (pintype "passive"))
    )
    (net (code "89") (name "Net-(J16-Pad1)") (class "Default")
      (node (ref "J16") (pin "1") (pinfunction "1_1") (pintype "output"))
      (node (ref "R34") (pin "1") (pinfunction "1_1") (pintype "passive"))
    )
    (net (code "90") (name "Net-(J17-Pad1)") (class "Default")
      (node (ref "J17") (pin "1") (pinfunction "1_1") (pintype "passive"))
      (node (ref "R6") (pin "1") (pinfunction "1_1") (pintype "passive"))
    )
    (net (code "91") (name "Net-(J18-Pad1)") (class "Default")
      (node (ref "J18") (pin "1") (pinfunction "1_1") (pintype "passive"))
      (node (ref "R11") (pin "1") (pinfunction "1_1") (pintype "passive"))
    )
    (net (code "92") (name "Net-(K1-COIL_2)") (class "Default")
      (node (ref "K1") (pin "4") (pinfunction "COIL_2_4") (pintype "passive"))
      (node (ref "Q1") (pin "3") (pinfunction "C_3") (pintype "passive"))
      (node (ref "Z1") (pin "2") (pinfunction "A_2") (pintype "passive"))
    )
    (net (code "93") (name "Net-(K1-COM)") (class "Default")
      (node (ref "J5") (pin "1") (pinfunction "1_1") (pintype "passive"))
      (node (ref "K1") (pin "5") (pinfunction "COM_5") (pintype "passive"))
    )
    (net (code "94") (name "Net-(K1-N.O.)") (class "Default")
      (node (ref "J5") (pin "2") (pinfunction "2_2") (pintype "passive"))
      (node (ref "K1") (pin "2") (pinfunction "N.O._2") (pintype "passive"))
    )
    (net (code "95") (name "Net-(K2-COIL_2)") (class "Default")
      (node (ref "K2") (pin "4") (pinfunction "COIL_2_4") (pintype "passive"))
      (node (ref "Q3") (pin "3") (pinfunction "C_3") (pintype "passive"))
      (node (ref "Z3") (pin "2") (pinfunction "A_2") (pintype "passive"))
    )
    (net (code "96") (name "Net-(K2-COM)") (class "Default")
      (node (ref "J10") (pin "1") (pinfunction "1_1") (pintype "passive"))
      (node (ref "K2") (pin "5") (pinfunction "COM_5") (pintype "passive"))
    )
    (net (code "97") (name "Net-(K2-N.O.)") (class "Default")
      (node (ref "J10") (pin "2") (pinfunction "2_2") (pintype "passive"))
      (node (ref "K2") (pin "2") (pinfunction "N.O._2") (pintype "passive"))
    )
    (net (code "98") (name "Net-(K3-COIL_2)") (class "Default")
      (node (ref "K3") (pin "4") (pinfunction "COIL_2_4") (pintype "passive"))
      (node (ref "Q4") (pin "3") (pinfunction "C_3") (pintype "passive"))
      (node (ref "Z4") (pin "2") (pinfunction "A_2") (pintype "passive"))
    )
    (net (code "99") (name "Net-(K3-COM)") (class "Default")
      (node (ref "F2") (pin "2") (pinfunction "2_2") (pintype "passive"))
      (node (ref "K3") (pin "5") (pinfunction "COM_5") (pintype "passive"))
    )
    (net (code "100") (name "Net-(K3-N.O.)") (class "Default")
      (node (ref "J13") (pin "1") (pinfunction "1_1") (pintype "passive"))
      (node (ref "K3") (pin "2") (pinfunction "N.O._2") (pintype "passive"))
    )
    (net (code "101") (name "Net-(LED1-A_GREEN)") (class "Default")
      (node (ref "LED1") (pin "1") (pinfunction "A_GREEN_1") (pintype "passive"))
      (node (ref "R8") (pin "2") (pinfunction "2_2") (pintype "passive"))
    )
    (net (code "102") (name "Net-(LED1-A_RED)") (class "Default")
      (node (ref "LED1") (pin "2") (pinfunction "A_RED_2") (pintype "passive"))
      (node (ref "R10") (pin "2") (pinfunction "2_2") (pintype "passive"))
    )
    (net (code "103") (name "Net-(LED2-A_GREEN)") (class "Default")
      (node (ref "LED2") (pin "1") (pinfunction "A_GREEN_1") (pintype "passive"))
      (node (ref "R16") (pin "2") (pinfunction "2_2") (pintype "passive"))
    )
    (net (code "104") (name "Net-(LED2-A_RED)") (class "Default")
      (node (ref "LED2") (pin "2") (pinfunction "A_RED_2") (pintype "passive"))
      (node (ref "R17") (pin "2") (pinfunction "2_2") (pintype "passive"))
    )
    (net (code "105") (name "Net-(LED3-A_GREEN)") (class "Default")
      (node (ref "LED3") (pin "1") (pinfunction "A_GREEN_1") (pintype "passive"))
      (node (ref "R20") (pin "2") (pinfunction "2_2") (pintype "passive"))
    )
    (net (code "106") (name "Net-(LED3-A_RED)") (class "Default")
      (node (ref "LED3") (pin "2") (pinfunction "A_RED_2") (pintype "passive"))
      (node (ref "R21") (pin "2") (pinfunction "2_2") (pintype "passive"))
    )
    (net (code "107") (name "Net-(PS1-+VIN)") (class "Default")
      (node (ref "C23") (pin "1") (pinfunction "1_1") (pintype "passive"))
      (node (ref "L2") (pin "2") (pinfunction "2_2") (pintype "passive"))
      (node (ref "PS1") (pin "1") (pinfunction "+VIN_1") (pintype "input"))
    )
    (net (code "108") (name "Net-(Q1-B)") (class "Default")
      (node (ref "Q1") (pin "1") (pinfunction "B_1") (pintype "passive"))
      (node (ref "R5") (pin "2") (pinfunction "2_2") (pintype "passive"))
    )
    (net (code "109") (name "Net-(Q2-G)") (class "Default")
      (node (ref "Q2") (pin "1") (pinfunction "G_1") (pintype "passive"))
      (node (ref "R9") (pin "2") (pinfunction "2_2") (pintype "passive"))
      (node (ref "Z2") (pin "2") (pinfunction "A_2") (pintype "passive"))
    )
    (net (code "110") (name "Net-(Q2-S)") (class "Default")
      (node (ref "FL1") (pin "1") (pinfunction "1_1") (pintype "passive"))
      (node (ref "Q2") (pin "3") (pinfunction "S_3") (pintype "passive"))
      (node (ref "Z2") (pin "1") (pinfunction "C_1") (pintype "passive"))
    )
    (net (code "111") (name "Net-(Q3-B)") (class "Default")
      (node (ref "Q3") (pin "1") (pinfunction "B_1") (pintype "passive"))
      (node (ref "R14") (pin "2") (pinfunction "2_2") (pintype "passive"))
    )
    (net (code "112") (name "Net-(Q4-B)") (class "Default")
      (node (ref "Q4") (pin "1") (pinfunction "B_1") (pintype "passive"))
      (node (ref "R19") (pin "2") (pinfunction "2_2") (pintype "passive"))
    )
    (net (code "113") (name "unconnected-(IC1-AGND-Pad46)") (class "Default")
      (node (ref "IC1") (pin "46") (pinfunction "AGND_46") (pintype "passive"))
    )
    (net (code "114") (name "unconnected-(IC1-EP-Pad49)") (class "Default")
      (node (ref "IC1") (pin "49") (pinfunction "EP_49") (pintype "passive"))
    )
    (net (code "115") (name "unconnected-(IC1-GPIO0-Pad11)") (class "Default")
      (node (ref "IC1") (pin "11") (pinfunction "GPIO0_11") (pintype "passive"))
    )
    (net (code "116") (name "unconnected-(IC1-GPIO1-Pad12)") (class "Default")
      (node (ref "IC1") (pin "12") (pinfunction "GPIO1_12") (pintype "passive"))
    )
    (net (code "117") (name "unconnected-(IC1-GPIO2-Pad13)") (class "Default")
      (node (ref "IC1") (pin "13") (pinfunction "GPIO2_13") (pintype "passive"))
    )
    (net (code "118") (name "unconnected-(IC1-GPIO3-Pad14)") (class "Default")
      (node (ref "IC1") (pin "14") (pinfunction "GPIO3_14") (pintype "passive"))
    )
    (net (code "119") (name "unconnected-(IC1-GPIO4-Pad19)") (class "Default")
      (node (ref "IC1") (pin "19") (pinfunction "GPIO4_19") (pintype "passive"))
    )
    (net (code "120") (name "unconnected-(IC1-GPIO5-Pad20)") (class "Default")
      (node (ref "IC1") (pin "20") (pinfunction "GPIO5_20") (pintype "passive"))
    )
    (net (code "121") (name "unconnected-(IC1-GPIO6-Pad21)") (class "Default")
      (node (ref "IC1") (pin "21") (pinfunction "GPIO6_21") (pintype "passive"))
    )
    (net (code "122") (name "unconnected-(IC1-GPIO7-Pad22)") (class "Default")
      (node (ref "IC1") (pin "22") (pinfunction "GPIO7_22") (pintype "passive"))
    )
    (net (code "123") (name "unconnected-(IC1-GPIO8-Pad27)") (class "Default")
      (node (ref "IC1") (pin "27") (pinfunction "GPIO8_27") (pintype "passive"))
    )
    (net (code "124") (name "unconnected-(IC1-GPIO9-Pad28)") (class "Default")
      (node (ref "IC1") (pin "28") (pinfunction "GPIO9_28") (pintype "passive"))
    )
    (net (code "125") (name "unconnected-(IC1-GPIO10-Pad29)") (class "Default")
      (node (ref "IC1") (pin "29") (pinfunction "GPIO10_29") (pintype "passive"))
    )
    (net (code "126") (name "unconnected-(IC1-GPIO11-Pad30)") (class "Default")
      (node (ref "IC1") (pin "30") (pinfunction "GPIO11_30") (pintype "passive"))
    )
    (net (code "127") (name "unconnected-(IC1-GPIO12-Pad35)") (class "Default")
      (node (ref "IC1") (pin "35") (pinfunction "GPIO12_35") (pintype "passive"))
    )
    (net (code "128") (name "unconnected-(IC1-GPIO13-Pad36)") (class "Default")
      (node (ref "IC1") (pin "36") (pinfunction "GPIO13_36") (pintype "passive"))
    )
    (net (code "129") (name "unconnected-(IC1-GPIO14-Pad37)") (class "Default")
      (node (ref "IC1") (pin "37") (pinfunction "GPIO14_37") (pintype "passive"))
    )
    (net (code "130") (name "unconnected-(IC1-GPIO15-Pad38)") (class "Default")
      (node (ref "IC1") (pin "38") (pinfunction "GPIO15_38") (pintype "passive"))
    )
    (net (code "131") (name "unconnected-(IC1-TX0-Pad18)") (class "Default")
      (node (ref "IC1") (pin "18") (pinfunction "TX0_18") (pintype "passive"))
    )
    (net (code "132") (name "unconnected-(IC1-TX1-Pad26)") (class "Default")
      (node (ref "IC1") (pin "26") (pinfunction "TX1_26") (pintype "passive"))
    )
    (net (code "133") (name "unconnected-(IC1-TX2-Pad34)") (class "Default")
      (node (ref "IC1") (pin "34") (pinfunction "TX2_34") (pintype "passive"))
    )
    (net (code "134") (name "unconnected-(IC1-TX3-Pad42)") (class "Default")
      (node (ref "IC1") (pin "42") (pinfunction "TX3_42") (pintype "passive"))
    )
    (net (code "135") (name "unconnected-(IC1-~{CTS0}-Pad16)") (class "Default")
      (node (ref "IC1") (pin "16") (pinfunction "~{CTS0}_16") (pintype "passive"))
    )
    (net (code "136") (name "unconnected-(IC1-~{CTS1}-Pad24)") (class "Default")
      (node (ref "IC1") (pin "24") (pinfunction "~{CTS1}_24") (pintype "passive"))
    )
    (net (code "137") (name "unconnected-(IC1-~{CTS2}-Pad32)") (class "Default")
      (node (ref "IC1") (pin "32") (pinfunction "~{CTS2}_32") (pintype "passive"))
    )
    (net (code "138") (name "unconnected-(IC1-~{CTS3}-Pad40)") (class "Default")
      (node (ref "IC1") (pin "40") (pinfunction "~{CTS3}_40") (pintype "passive"))
    )
    (net (code "139") (name "unconnected-(IC1-~{IRQ}-Pad7)") (class "Default")
      (node (ref "IC1") (pin "7") (pinfunction "~{IRQ}_7") (pintype "passive"))
    )
    (net (code "140") (name "unconnected-(IC1-~{RST}-Pad8)") (class "Default")
      (node (ref "IC1") (pin "8") (pinfunction "~{RST}_8") (pintype "passive"))
    )
    (net (code "141") (name "unconnected-(IC1-~{RTS0}-Pad15)") (class "Default")
      (node (ref "IC1") (pin "15") (pinfunction "~{RTS0}_15") (pintype "passive"))
    )
    (net (code "142") (name "unconnected-(IC1-~{RTS1}-Pad23)") (class "Default")
      (node (ref "IC1") (pin "23") (pinfunction "~{RTS1}_23") (pintype "passive"))
    )
    (net (code "143") (name "unconnected-(IC1-~{RTS2}-Pad31)") (class "Default")
      (node (ref "IC1") (pin "31") (pinfunction "~{RTS2}_31") (pintype "passive"))
    )
    (net (code "144") (name "unconnected-(IC1-~{RTS3}-Pad39)") (class "Default")
      (node (ref "IC1") (pin "39") (pinfunction "~{RTS3}_39") (pintype "passive"))
    )
    (net (code "145") (name "unconnected-(IC2-PGOOD-Pad2)") (class "Default")
      (node (ref "IC2") (pin "2") (pinfunction "PGOOD_2") (pintype "passive"))
    )
    (net (code "146") (name "unconnected-(IC5-AIN2-Pad6)") (class "Default")
      (node (ref "IC5") (pin "6") (pinfunction "AIN2_6") (pintype "passive+no_connect"))
    )
    (net (code "147") (name "unconnected-(IC5-AIN3-Pad7)") (class "Default")
      (node (ref "IC5") (pin "7") (pinfunction "AIN3_7") (pintype "passive+no_connect"))
    )
    (net (code "148") (name "unconnected-(IC5-ALERT{slash}RDY-Pad2)") (class "Default")
      (node (ref "IC5") (pin "2") (pinfunction "ALERT/RDY_2") (pintype "passive"))
    )
    (net (code "149") (name "unconnected-(IC7-CHR0-Pad15)") (class "Default")
      (node (ref "IC7") (pin "15") (pinfunction "CHR0_15") (pintype "passive"))
    )
    (net (code "150") (name "unconnected-(IC7-CHR1-Pad14)") (class "Default")
      (node (ref "IC7") (pin "14") (pinfunction "CHR1_14") (pintype "passive"))
    )
    (net (code "151") (name "unconnected-(IC7-CHREN-Pad13)") (class "Default")
      (node (ref "IC7") (pin "13") (pinfunction "CHREN_13") (pintype "passive"))
    )
    (net (code "152") (name "unconnected-(IC7-CTS-Pad23)") (class "Default")
      (node (ref "IC7") (pin "23") (pinfunction "CTS_23") (pintype "passive"))
    )
    (net (code "153") (name "unconnected-(IC7-DCD-Pad1)") (class "Default")
      (node (ref "IC7") (pin "1") (pinfunction "DCD_1") (pintype "passive"))
    )
    (net (code "154") (name "unconnected-(IC7-DSR-Pad27)") (class "Default")
      (node (ref "IC7") (pin "27") (pinfunction "DSR_27") (pintype "passive"))
    )
    (net (code "155") (name "unconnected-(IC7-GPIO.0_{slash}_TXT-Pad19)") (class "Default")
      (node (ref "IC7") (pin "19") (pinfunction "GPIO.0_/_TXT_19") (pintype "passive"))
    )
    (net (code "156") (name "unconnected-(IC7-GPIO.1_{slash}_RXT-Pad18)") (class "Default")
      (node (ref "IC7") (pin "18") (pinfunction "GPIO.1_/_RXT_18") (pintype "passive"))
    )
    (net (code "157") (name "unconnected-(IC7-GPIO.2_{slash}_RS485-Pad17)") (class "Default")
      (node (ref "IC7") (pin "17") (pinfunction "GPIO.2_/_RS485_17") (pintype "passive"))
    )
    (net (code "158") (name "unconnected-(IC7-GPIO.3_{slash}_WAKEUP-Pad16)") (class "Default")
      (node (ref "IC7") (pin "16") (pinfunction "GPIO.3_/_WAKEUP_16") (pintype "passive"))
    )
    (net (code "159") (name "unconnected-(IC7-GPIO.4-Pad22)") (class "Default")
      (node (ref "IC7") (pin "22") (pinfunction "GPIO.4_22") (pintype "passive"))
    )
    (net (code "160") (name "unconnected-(IC7-GPIO.5-Pad21)") (class "Default")
      (node (ref "IC7") (pin "21") (pinfunction "GPIO.5_21") (pintype "passive"))
    )
    (net (code "161") (name "unconnected-(IC7-GPIO.6-Pad20)") (class "Default")
      (node (ref "IC7") (pin "20") (pinfunction "GPIO.6_20") (pintype "passive"))
    )
    (net (code "162") (name "unconnected-(IC7-NC-Pad10)") (class "Default")
      (node (ref "IC7") (pin "10") (pinfunction "NC_10") (pintype "passive"))
    )
    (net (code "163") (name "unconnected-(IC7-RI_{slash}_CLK-Pad2)") (class "Default")
      (node (ref "IC7") (pin "2") (pinfunction "RI_/_CLK_2") (pintype "passive"))
    )
    (net (code "164") (name "unconnected-(IC7-SUSPEND-Pad12)") (class "Default")
      (node (ref "IC7") (pin "12") (pinfunction "SUSPEND_12") (pintype "passive"))
    )
    (net (code "165") (name "unconnected-(IC11-AIN2-Pad6)") (class "Default")
      (node (ref "IC11") (pin "6") (pinfunction "AIN2_6") (pintype "passive+no_connect"))
    )
    (net (code "166") (name "unconnected-(IC11-AIN3-Pad7)") (class "Default")
      (node (ref "IC11") (pin "7") (pinfunction "AIN3_7") (pintype "passive+no_connect"))
    )
    (net (code "167") (name "unconnected-(IC11-ALERT{slash}RDY-Pad2)") (class "Default")
      (node (ref "IC11") (pin "2") (pinfunction "ALERT/RDY_2") (pintype "passive"))
    )
    (net (code "168") (name "unconnected-(J1-NC-Pad4)") (class "Default")
      (node (ref "J1") (pin "4") (pinfunction "NC_4") (pintype "passive+no_connect"))
    )
    (net (code "169") (name "unconnected-(J1-RX-Pad2)") (class "Default")
      (node (ref "J1") (pin "2") (pinfunction "RX_2") (pintype "passive"))
    )
    (net (code "170") (name "unconnected-(J6-NC-Pad4)") (class "Default")
      (node (ref "J6") (pin "4") (pinfunction "NC_4") (pintype "passive+no_connect"))
    )
    (net (code "171") (name "unconnected-(J6-RX-Pad2)") (class "Default")
      (node (ref "J6") (pin "2") (pinfunction "RX_2") (pintype "passive"))
    )
    (net (code "172") (name "unconnected-(J7-NC-Pad4)") (class "Default")
      (node (ref "J7") (pin "4") (pinfunction "NC_4") (pintype "passive+no_connect"))
    )
    (net (code "173") (name "unconnected-(J7-RX-Pad2)") (class "Default")
      (node (ref "J7") (pin "2") (pinfunction "RX_2") (pintype "passive"))
    )
    (net (code "174") (name "unconnected-(J8-Pad3)") (class "Default")
      (node (ref "J8") (pin "3") (pinfunction "3_3") (pintype "passive"))
    )
    (net (code "175") (name "unconnected-(J8-Pad4)") (class "Default")
      (node (ref "J8") (pin "4") (pinfunction "4_4") (pintype "passive"))
    )
    (net (code "176") (name "unconnected-(J9-NC-Pad4)") (class "Default")
      (node (ref "J9") (pin "4") (pinfunction "NC_4") (pintype "passive+no_connect"))
    )
    (net (code "177") (name "unconnected-(J9-RX-Pad2)") (class "Default")
      (node (ref "J9") (pin "2") (pinfunction "RX_2") (pintype "passive"))
    )
    (net (code "178") (name "unconnected-(J11-Pad1)") (class "Default")
      (node (ref "J11") (pin "1") (pinfunction "1_1") (pintype "passive"))
    )
    (net (code "179") (name "unconnected-(J11-Pad6)") (class "Default")
      (node (ref "J11") (pin "6") (pinfunction "6_6") (pintype "passive"))
    )
    (net (code "180") (name "unconnected-(J19-CC1-PadA5)") (class "Default")
      (node (ref "J19") (pin "A5") (pinfunction "CC1_A5") (pintype "passive"))
    )
    (net (code "181") (name "unconnected-(J19-CC2-PadB5)") (class "Default")
      (node (ref "J19") (pin "B5") (pinfunction "CC2_B5") (pintype "passive"))
    )
    (net (code "182") (name "unconnected-(J19-DUMMY_1-Pad1)") (class "Default")
      (node (ref "J19") (pin "1") (pinfunction "DUMMY_1_1") (pintype "passive"))
    )
    (net (code "183") (name "unconnected-(J19-DUMMY_2-Pad2)") (class "Default")
      (node (ref "J19") (pin "2") (pinfunction "DUMMY_2_2") (pintype "passive"))
    )
    (net (code "184") (name "unconnected-(J19-DUMMY_3-Pad3)") (class "Default")
      (node (ref "J19") (pin "3") (pinfunction "DUMMY_3_3") (pintype "passive"))
    )
    (net (code "185") (name "unconnected-(J19-DUMMY_4-Pad4)") (class "Default")
      (node (ref "J19") (pin "4") (pinfunction "DUMMY_4_4") (pintype "passive"))
    )
    (net (code "186") (name "unconnected-(J19-SBU1-PadA8)") (class "Default")
      (node (ref "J19") (pin "A8") (pinfunction "SBU1_A8") (pintype "passive"))
    )
    (net (code "187") (name "unconnected-(J19-SBU2-PadB8)") (class "Default")
      (node (ref "J19") (pin "B8") (pinfunction "SBU2_B8") (pintype "passive"))
    )
    (net (code "188") (name "unconnected-(J19-VBUS_4-PadB9)") (class "Default")
      (node (ref "J19") (pin "B9") (pinfunction "VBUS_4_B9") (pintype "passive"))
    )
    (net (code "189") (name "unconnected-(K1-N.C.-Pad3)") (class "Default")
      (node (ref "K1") (pin "3") (pinfunction "N.C._3") (pintype "passive"))
    )
    (net (code "190") (name "unconnected-(K2-N.C.-Pad3)") (class "Default")
      (node (ref "K2") (pin "3") (pinfunction "N.C._3") (pintype "passive"))
    )
    (net (code "191") (name "unconnected-(K3-N.C.-Pad3)") (class "Default")
      (node (ref "K3") (pin "3") (pinfunction "N.C._3") (pintype "passive"))
    )
    (net (code "192") (name "unconnected-(PS1-NC-Pad4)") (class "Default")
      (node (ref "PS1") (pin "4") (pinfunction "NC_4") (pintype "passive"))
    )
    (net (code "193") (name "unconnected-(S1-COM_2-Pad4)") (class "Default")
      (node (ref "S1") (pin "4") (pinfunction "COM_2_4") (pintype "passive"))
    )
    (net (code "194") (name "unconnected-(S1-NO_2-Pad2)") (class "Default")
      (node (ref "S1") (pin "2") (pinfunction "NO_2_2") (pintype "passive"))
    )
    (net (code "195") (name "unconnected-(S2-COM_2-Pad4)") (class "Default")
      (node (ref "S2") (pin "4") (pinfunction "COM_2_4") (pintype "passive"))
    )
    (net (code "196") (name "unconnected-(S2-NO_2-Pad2)") (class "Default")
      (node (ref "S2") (pin "2") (pinfunction "NO_2_2") (pintype "passive"))
    )
  )
)
